# LEDs.net
KiCad netlist of a schematic drawn in Altium Designer
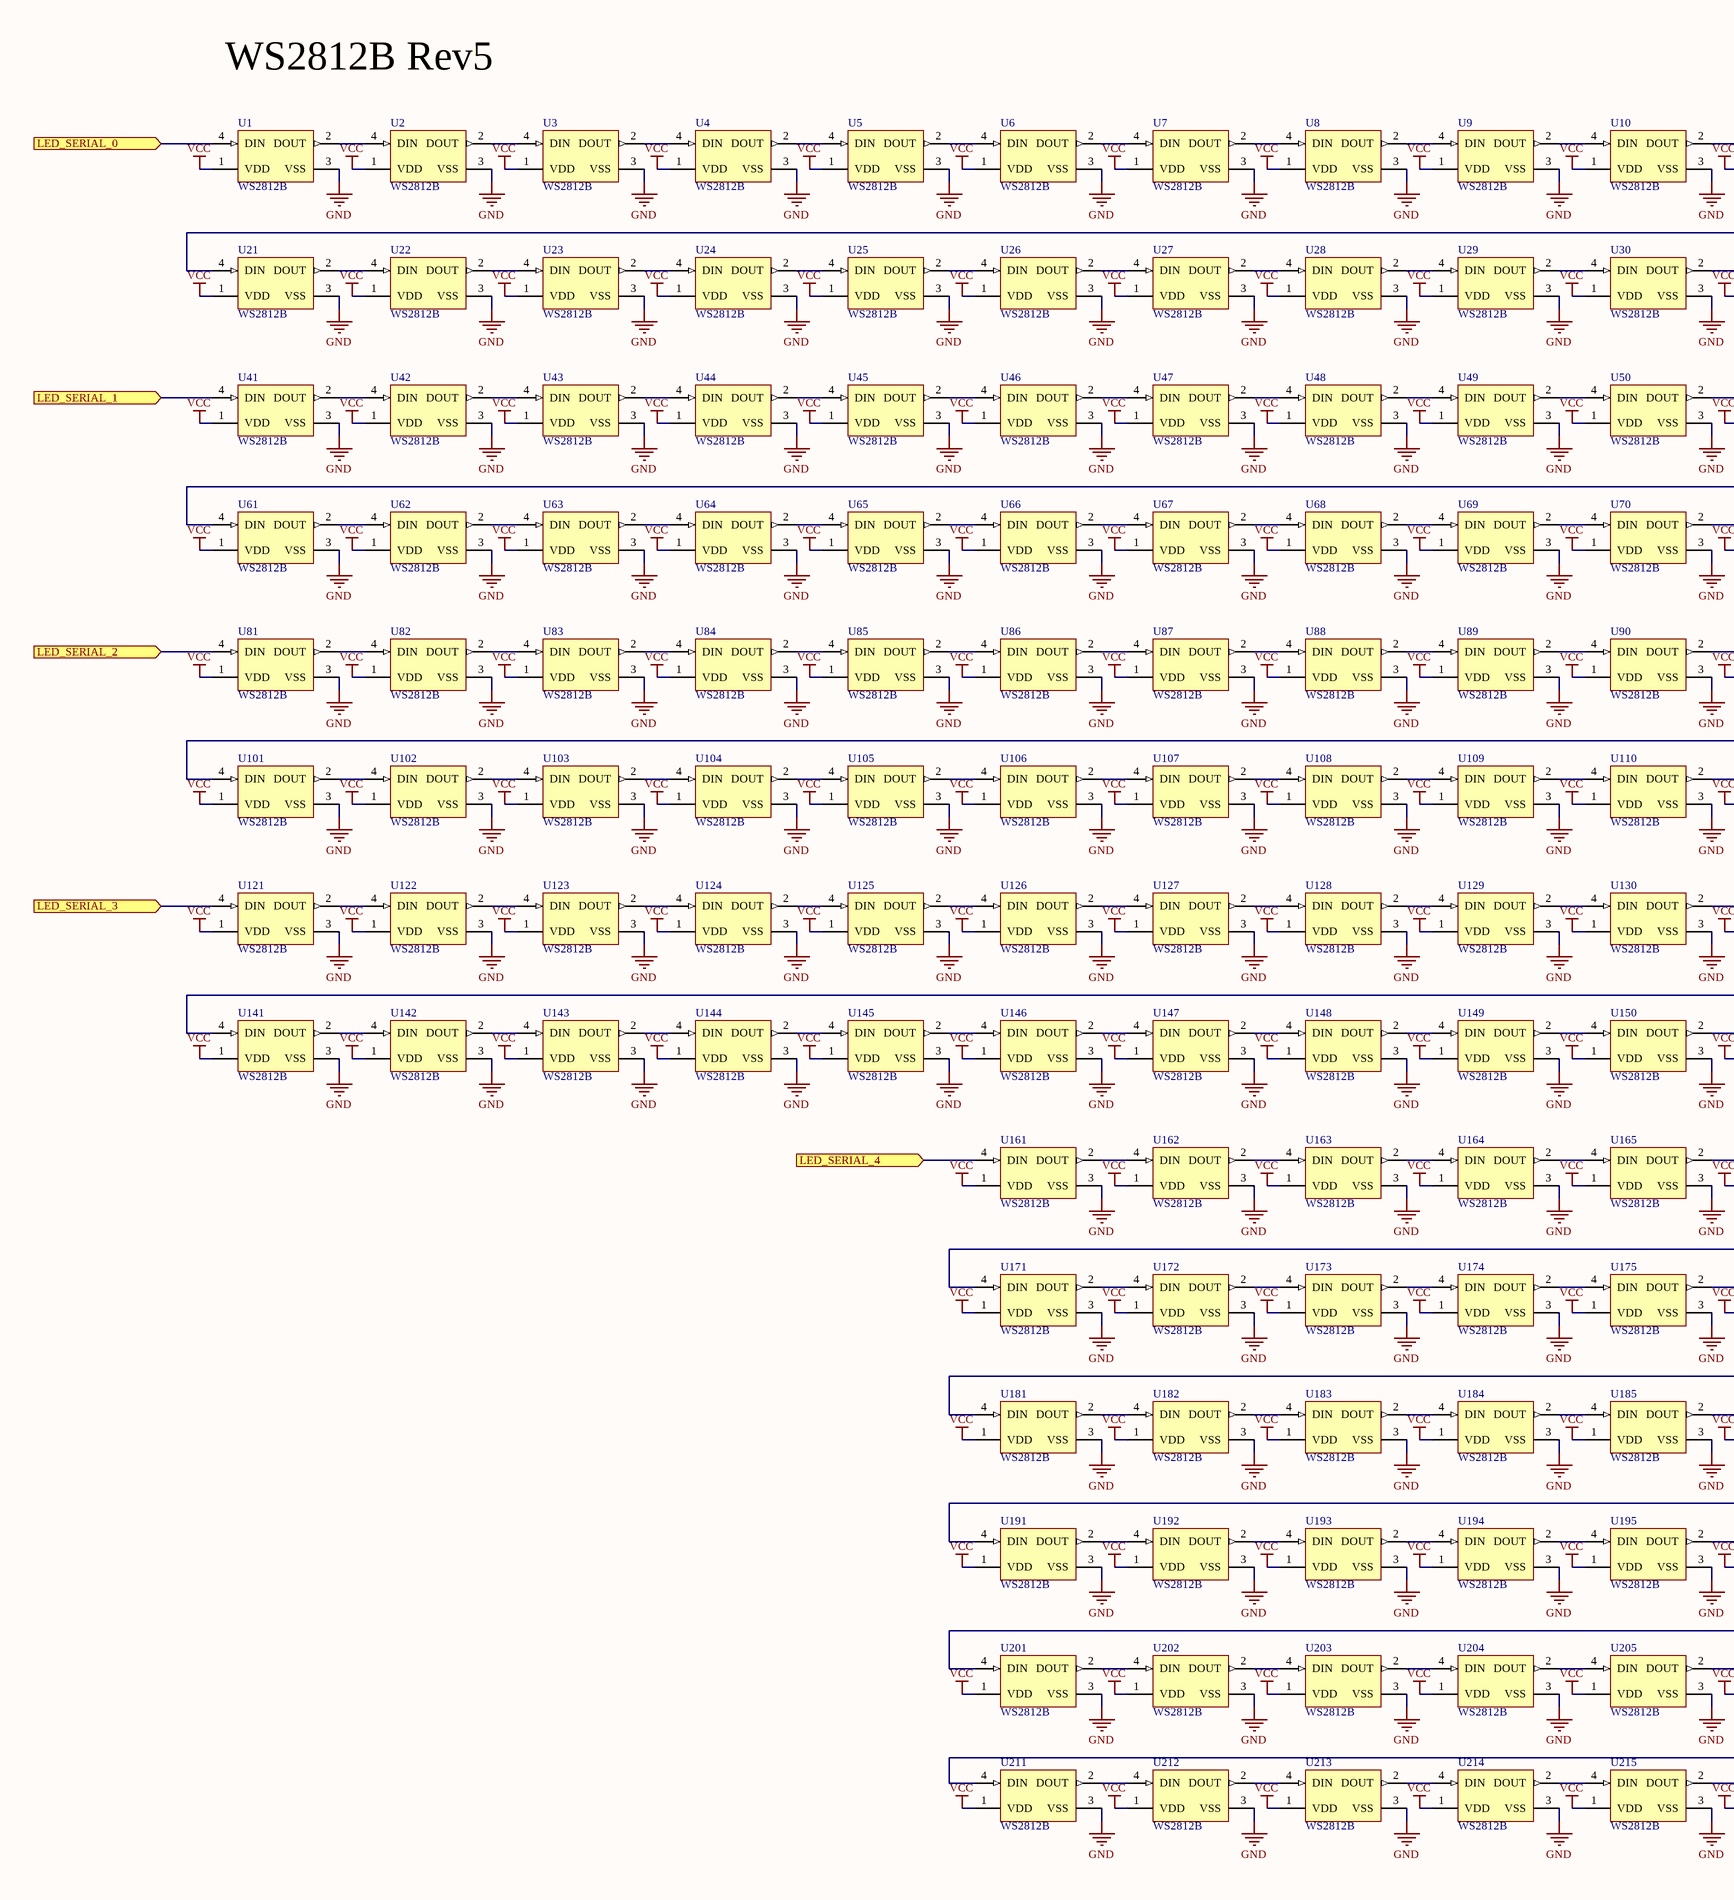
[diagram p0: LEDs.SchDoc, left]
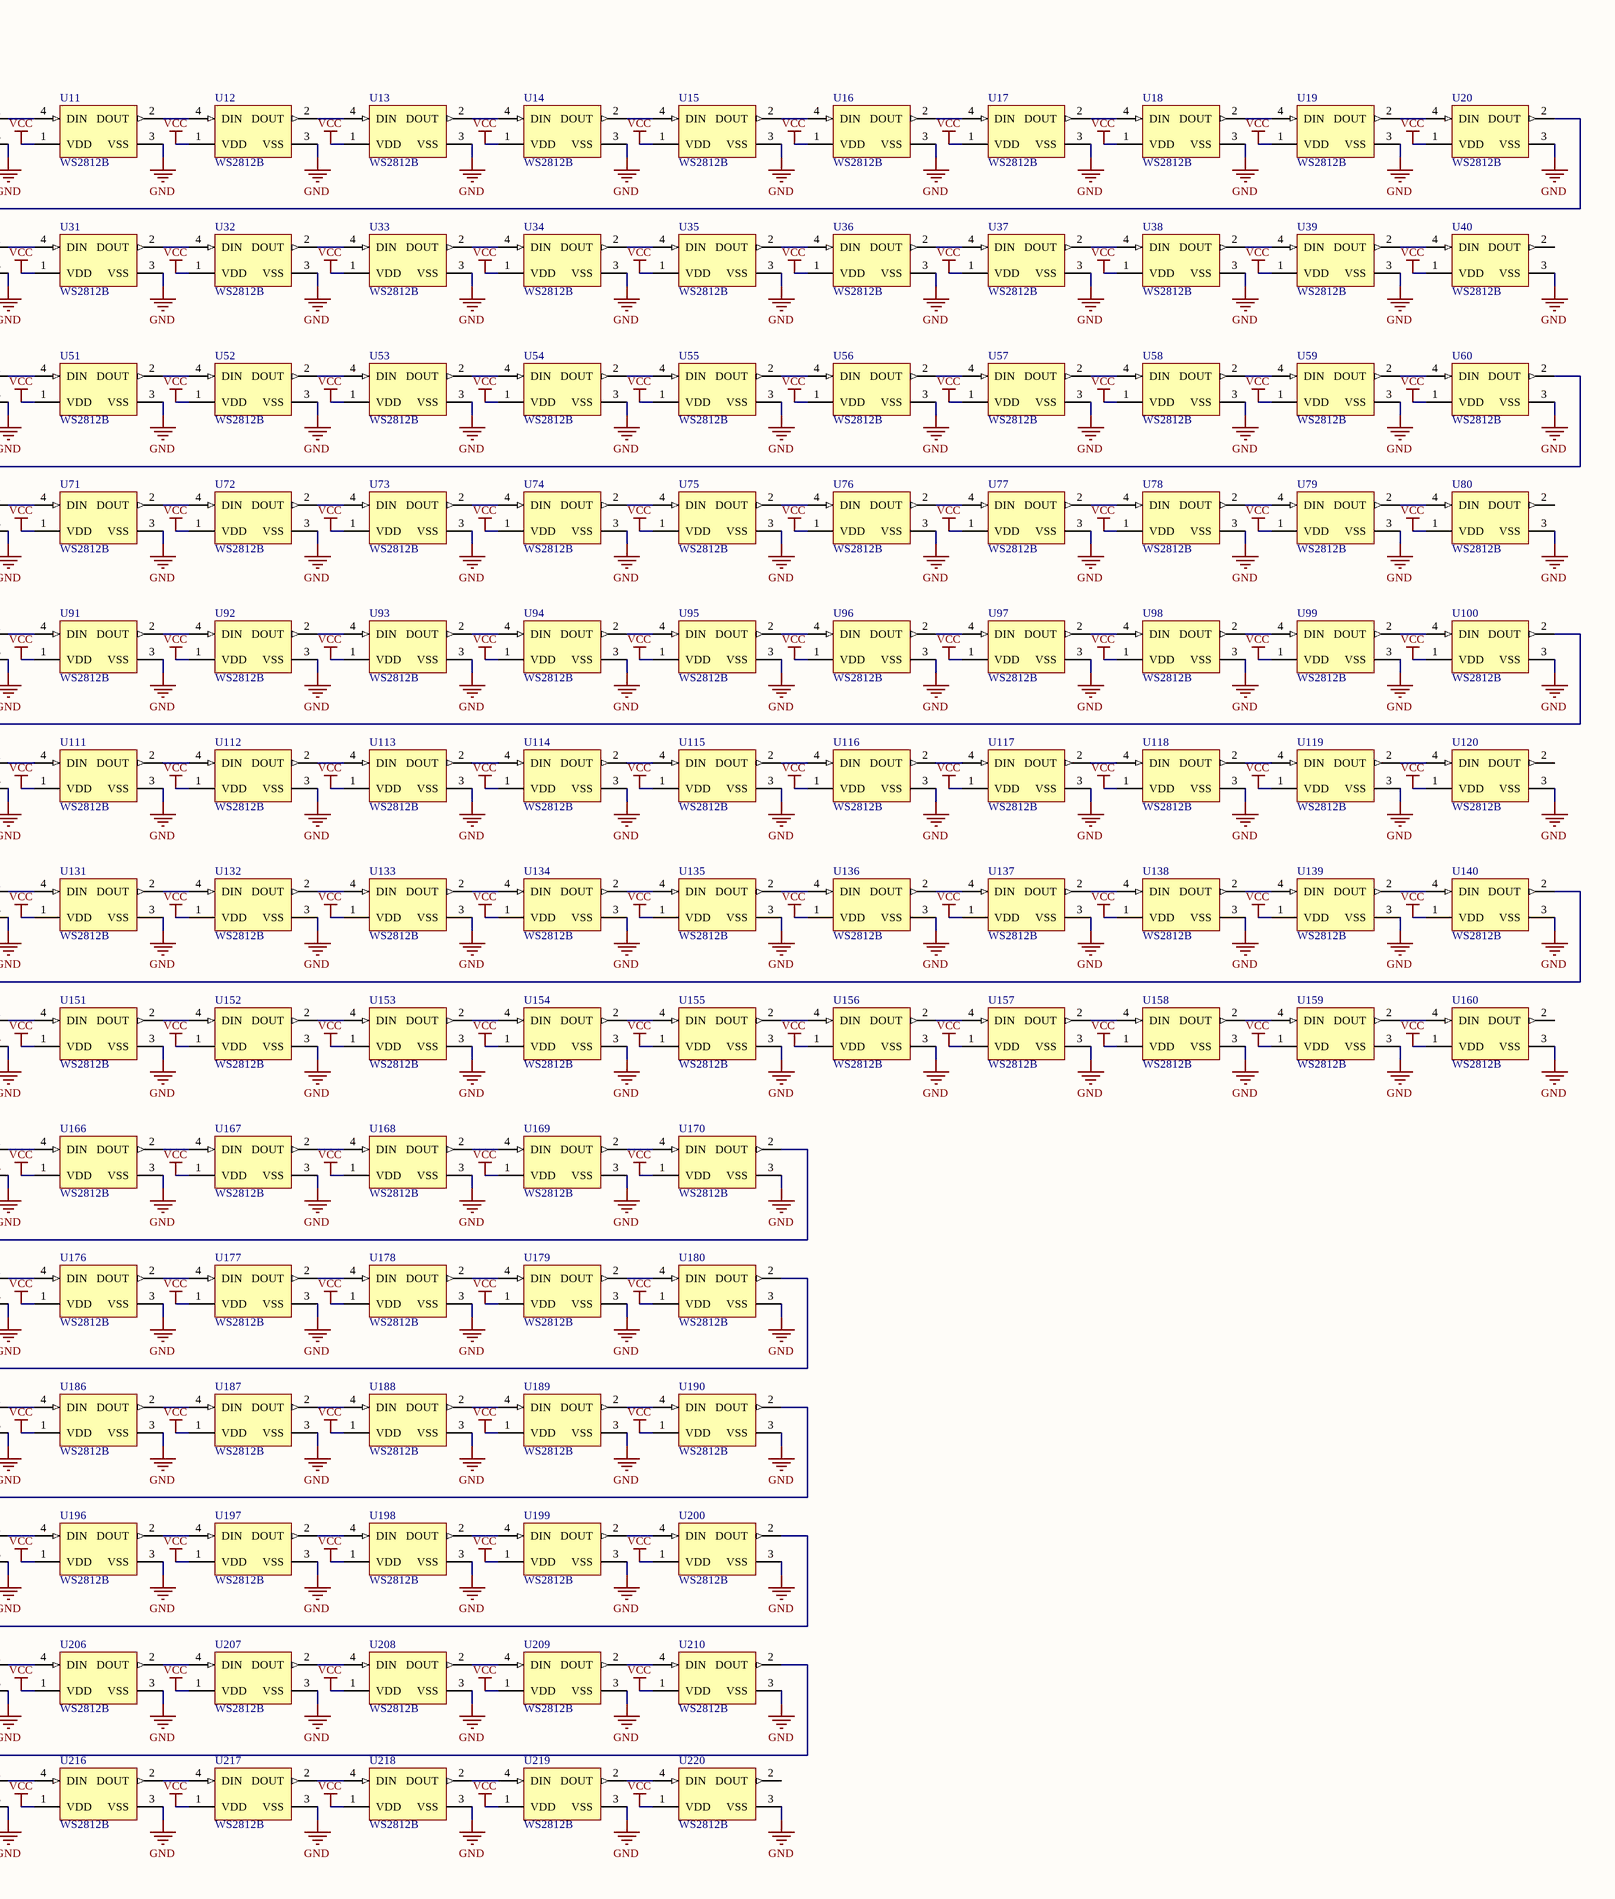
[diagram p1: LEDs.SchDoc, right]

(export (version "E")
  (design (tool "Eeschema 10.0.6"))
  (components
    (comp (ref "U1")
      (value "WS2812B")
      (footprint "LED5050")
      (fields (field (name "MANUFACTURER") "Adafruit-Industries-LLC") (field (name "LCSC PART #") "C114586"))
      (libsource (lib "Schlib1") (part "CMP-2000-05026-1"))
    )
    (comp (ref "U2")
      (value "WS2812B")
      (footprint "LED5050")
      (fields (field (name "MANUFACTURER") "Adafruit-Industries-LLC") (field (name "LCSC PART #") "C114586"))
      (libsource (lib "Schlib1") (part "CMP-2000-05026-1"))
    )
    (comp (ref "U3")
      (value "WS2812B")
      (footprint "LED5050")
      (fields (field (name "MANUFACTURER") "Adafruit-Industries-LLC") (field (name "LCSC PART #") "C114586"))
      (libsource (lib "Schlib1") (part "CMP-2000-05026-1"))
    )
    (comp (ref "U4")
      (value "WS2812B")
      (footprint "LED5050")
      (fields (field (name "MANUFACTURER") "Adafruit-Industries-LLC") (field (name "LCSC PART #") "C114586"))
      (libsource (lib "Schlib1") (part "CMP-2000-05026-1"))
    )
    (comp (ref "U5")
      (value "WS2812B")
      (footprint "LED5050")
      (fields (field (name "MANUFACTURER") "Adafruit-Industries-LLC") (field (name "LCSC PART #") "C114586"))
      (libsource (lib "Schlib1") (part "CMP-2000-05026-1"))
    )
    (comp (ref "U6")
      (value "WS2812B")
      (footprint "LED5050")
      (fields (field (name "MANUFACTURER") "Adafruit-Industries-LLC") (field (name "LCSC PART #") "C114586"))
      (libsource (lib "Schlib1") (part "CMP-2000-05026-1"))
    )
    (comp (ref "U7")
      (value "WS2812B")
      (footprint "LED5050")
      (fields (field (name "MANUFACTURER") "Adafruit-Industries-LLC") (field (name "LCSC PART #") "C114586"))
      (libsource (lib "Schlib1") (part "CMP-2000-05026-1"))
    )
    (comp (ref "U8")
      (value "WS2812B")
      (footprint "LED5050")
      (fields (field (name "MANUFACTURER") "Adafruit-Industries-LLC") (field (name "LCSC PART #") "C114586"))
      (libsource (lib "Schlib1") (part "CMP-2000-05026-1"))
    )
    (comp (ref "U9")
      (value "WS2812B")
      (footprint "LED5050")
      (fields (field (name "MANUFACTURER") "Adafruit-Industries-LLC") (field (name "LCSC PART #") "C114586"))
      (libsource (lib "Schlib1") (part "CMP-2000-05026-1"))
    )
    (comp (ref "U10")
      (value "WS2812B")
      (footprint "LED5050")
      (fields (field (name "MANUFACTURER") "Adafruit-Industries-LLC") (field (name "LCSC PART #") "C114586"))
      (libsource (lib "Schlib1") (part "CMP-2000-05026-1"))
    )
    (comp (ref "U11")
      (value "WS2812B")
      (footprint "LED5050")
      (fields (field (name "MANUFACTURER") "Adafruit-Industries-LLC") (field (name "LCSC PART #") "C114586"))
      (libsource (lib "Schlib1") (part "CMP-2000-05026-1"))
    )
    (comp (ref "U12")
      (value "WS2812B")
      (footprint "LED5050")
      (fields (field (name "MANUFACTURER") "Adafruit-Industries-LLC") (field (name "LCSC PART #") "C114586"))
      (libsource (lib "Schlib1") (part "CMP-2000-05026-1"))
    )
    (comp (ref "U13")
      (value "WS2812B")
      (footprint "LED5050")
      (fields (field (name "MANUFACTURER") "Adafruit-Industries-LLC") (field (name "LCSC PART #") "C114586"))
      (libsource (lib "Schlib1") (part "CMP-2000-05026-1"))
    )
    (comp (ref "U14")
      (value "WS2812B")
      (footprint "LED5050")
      (fields (field (name "MANUFACTURER") "Adafruit-Industries-LLC") (field (name "LCSC PART #") "C114586"))
      (libsource (lib "Schlib1") (part "CMP-2000-05026-1"))
    )
    (comp (ref "U15")
      (value "WS2812B")
      (footprint "LED5050")
      (fields (field (name "MANUFACTURER") "Adafruit-Industries-LLC") (field (name "LCSC PART #") "C114586"))
      (libsource (lib "Schlib1") (part "CMP-2000-05026-1"))
    )
    (comp (ref "U16")
      (value "WS2812B")
      (footprint "LED5050")
      (fields (field (name "MANUFACTURER") "Adafruit-Industries-LLC") (field (name "LCSC PART #") "C114586"))
      (libsource (lib "Schlib1") (part "CMP-2000-05026-1"))
    )
    (comp (ref "U17")
      (value "WS2812B")
      (footprint "LED5050")
      (fields (field (name "MANUFACTURER") "Adafruit-Industries-LLC") (field (name "LCSC PART #") "C114586"))
      (libsource (lib "Schlib1") (part "CMP-2000-05026-1"))
    )
    (comp (ref "U18")
      (value "WS2812B")
      (footprint "LED5050")
      (fields (field (name "MANUFACTURER") "Adafruit-Industries-LLC") (field (name "LCSC PART #") "C114586"))
      (libsource (lib "Schlib1") (part "CMP-2000-05026-1"))
    )
    (comp (ref "U19")
      (value "WS2812B")
      (footprint "LED5050")
      (fields (field (name "MANUFACTURER") "Adafruit-Industries-LLC") (field (name "LCSC PART #") "C114586"))
      (libsource (lib "Schlib1") (part "CMP-2000-05026-1"))
    )
    (comp (ref "U20")
      (value "WS2812B")
      (footprint "LED5050")
      (fields (field (name "MANUFACTURER") "Adafruit-Industries-LLC") (field (name "LCSC PART #") "C114586"))
      (libsource (lib "Schlib1") (part "CMP-2000-05026-1"))
    )
    (comp (ref "U21")
      (value "WS2812B")
      (footprint "LED5050")
      (fields (field (name "MANUFACTURER") "Adafruit-Industries-LLC") (field (name "LCSC PART #") "C114586"))
      (libsource (lib "Schlib1") (part "CMP-2000-05026-1"))
    )
    (comp (ref "U22")
      (value "WS2812B")
      (footprint "LED5050")
      (fields (field (name "MANUFACTURER") "Adafruit-Industries-LLC") (field (name "LCSC PART #") "C114586"))
      (libsource (lib "Schlib1") (part "CMP-2000-05026-1"))
    )
    (comp (ref "U23")
      (value "WS2812B")
      (footprint "LED5050")
      (fields (field (name "MANUFACTURER") "Adafruit-Industries-LLC") (field (name "LCSC PART #") "C114586"))
      (libsource (lib "Schlib1") (part "CMP-2000-05026-1"))
    )
    (comp (ref "U24")
      (value "WS2812B")
      (footprint "LED5050")
      (fields (field (name "MANUFACTURER") "Adafruit-Industries-LLC") (field (name "LCSC PART #") "C114586"))
      (libsource (lib "Schlib1") (part "CMP-2000-05026-1"))
    )
    (comp (ref "U25")
      (value "WS2812B")
      (footprint "LED5050")
      (fields (field (name "MANUFACTURER") "Adafruit-Industries-LLC") (field (name "LCSC PART #") "C114586"))
      (libsource (lib "Schlib1") (part "CMP-2000-05026-1"))
    )
    (comp (ref "U26")
      (value "WS2812B")
      (footprint "LED5050")
      (fields (field (name "MANUFACTURER") "Adafruit-Industries-LLC") (field (name "LCSC PART #") "C114586"))
      (libsource (lib "Schlib1") (part "CMP-2000-05026-1"))
    )
    (comp (ref "U27")
      (value "WS2812B")
      (footprint "LED5050")
      (fields (field (name "MANUFACTURER") "Adafruit-Industries-LLC") (field (name "LCSC PART #") "C114586"))
      (libsource (lib "Schlib1") (part "CMP-2000-05026-1"))
    )
    (comp (ref "U28")
      (value "WS2812B")
      (footprint "LED5050")
      (fields (field (name "MANUFACTURER") "Adafruit-Industries-LLC") (field (name "LCSC PART #") "C114586"))
      (libsource (lib "Schlib1") (part "CMP-2000-05026-1"))
    )
    (comp (ref "U29")
      (value "WS2812B")
      (footprint "LED5050")
      (fields (field (name "MANUFACTURER") "Adafruit-Industries-LLC") (field (name "LCSC PART #") "C114586"))
      (libsource (lib "Schlib1") (part "CMP-2000-05026-1"))
    )
    (comp (ref "U30")
      (value "WS2812B")
      (footprint "LED5050")
      (fields (field (name "MANUFACTURER") "Adafruit-Industries-LLC") (field (name "LCSC PART #") "C114586"))
      (libsource (lib "Schlib1") (part "CMP-2000-05026-1"))
    )
    (comp (ref "U31")
      (value "WS2812B")
      (footprint "LED5050")
      (fields (field (name "MANUFACTURER") "Adafruit-Industries-LLC") (field (name "LCSC PART #") "C114586"))
      (libsource (lib "Schlib1") (part "CMP-2000-05026-1"))
    )
    (comp (ref "U32")
      (value "WS2812B")
      (footprint "LED5050")
      (fields (field (name "MANUFACTURER") "Adafruit-Industries-LLC") (field (name "LCSC PART #") "C114586"))
      (libsource (lib "Schlib1") (part "CMP-2000-05026-1"))
    )
    (comp (ref "U33")
      (value "WS2812B")
      (footprint "LED5050")
      (fields (field (name "MANUFACTURER") "Adafruit-Industries-LLC") (field (name "LCSC PART #") "C114586"))
      (libsource (lib "Schlib1") (part "CMP-2000-05026-1"))
    )
    (comp (ref "U34")
      (value "WS2812B")
      (footprint "LED5050")
      (fields (field (name "MANUFACTURER") "Adafruit-Industries-LLC") (field (name "LCSC PART #") "C114586"))
      (libsource (lib "Schlib1") (part "CMP-2000-05026-1"))
    )
    (comp (ref "U35")
      (value "WS2812B")
      (footprint "LED5050")
      (fields (field (name "MANUFACTURER") "Adafruit-Industries-LLC") (field (name "LCSC PART #") "C114586"))
      (libsource (lib "Schlib1") (part "CMP-2000-05026-1"))
    )
    (comp (ref "U36")
      (value "WS2812B")
      (footprint "LED5050")
      (fields (field (name "MANUFACTURER") "Adafruit-Industries-LLC") (field (name "LCSC PART #") "C114586"))
      (libsource (lib "Schlib1") (part "CMP-2000-05026-1"))
    )
    (comp (ref "U37")
      (value "WS2812B")
      (footprint "LED5050")
      (fields (field (name "MANUFACTURER") "Adafruit-Industries-LLC") (field (name "LCSC PART #") "C114586"))
      (libsource (lib "Schlib1") (part "CMP-2000-05026-1"))
    )
    (comp (ref "U38")
      (value "WS2812B")
      (footprint "LED5050")
      (fields (field (name "MANUFACTURER") "Adafruit-Industries-LLC") (field (name "LCSC PART #") "C114586"))
      (libsource (lib "Schlib1") (part "CMP-2000-05026-1"))
    )
    (comp (ref "U39")
      (value "WS2812B")
      (footprint "LED5050")
      (fields (field (name "MANUFACTURER") "Adafruit-Industries-LLC") (field (name "LCSC PART #") "C114586"))
      (libsource (lib "Schlib1") (part "CMP-2000-05026-1"))
    )
    (comp (ref "U40")
      (value "WS2812B")
      (footprint "LED5050")
      (fields (field (name "MANUFACTURER") "Adafruit-Industries-LLC") (field (name "LCSC PART #") "C114586"))
      (libsource (lib "Schlib1") (part "CMP-2000-05026-1"))
    )
    (comp (ref "U41")
      (value "WS2812B")
      (footprint "LED5050")
      (fields (field (name "MANUFACTURER") "Adafruit-Industries-LLC") (field (name "LCSC PART #") "C114586"))
      (libsource (lib "Schlib1") (part "CMP-2000-05026-1"))
    )
    (comp (ref "U42")
      (value "WS2812B")
      (footprint "LED5050")
      (fields (field (name "MANUFACTURER") "Adafruit-Industries-LLC") (field (name "LCSC PART #") "C114586"))
      (libsource (lib "Schlib1") (part "CMP-2000-05026-1"))
    )
    (comp (ref "U43")
      (value "WS2812B")
      (footprint "LED5050")
      (fields (field (name "MANUFACTURER") "Adafruit-Industries-LLC") (field (name "LCSC PART #") "C114586"))
      (libsource (lib "Schlib1") (part "CMP-2000-05026-1"))
    )
    (comp (ref "U44")
      (value "WS2812B")
      (footprint "LED5050")
      (fields (field (name "MANUFACTURER") "Adafruit-Industries-LLC") (field (name "LCSC PART #") "C114586"))
      (libsource (lib "Schlib1") (part "CMP-2000-05026-1"))
    )
    (comp (ref "U45")
      (value "WS2812B")
      (footprint "LED5050")
      (fields (field (name "MANUFACTURER") "Adafruit-Industries-LLC") (field (name "LCSC PART #") "C114586"))
      (libsource (lib "Schlib1") (part "CMP-2000-05026-1"))
    )
    (comp (ref "U46")
      (value "WS2812B")
      (footprint "LED5050")
      (fields (field (name "MANUFACTURER") "Adafruit-Industries-LLC") (field (name "LCSC PART #") "C114586"))
      (libsource (lib "Schlib1") (part "CMP-2000-05026-1"))
    )
    (comp (ref "U47")
      (value "WS2812B")
      (footprint "LED5050")
      (fields (field (name "MANUFACTURER") "Adafruit-Industries-LLC") (field (name "LCSC PART #") "C114586"))
      (libsource (lib "Schlib1") (part "CMP-2000-05026-1"))
    )
    (comp (ref "U48")
      (value "WS2812B")
      (footprint "LED5050")
      (fields (field (name "MANUFACTURER") "Adafruit-Industries-LLC") (field (name "LCSC PART #") "C114586"))
      (libsource (lib "Schlib1") (part "CMP-2000-05026-1"))
    )
    (comp (ref "U49")
      (value "WS2812B")
      (footprint "LED5050")
      (fields (field (name "MANUFACTURER") "Adafruit-Industries-LLC") (field (name "LCSC PART #") "C114586"))
      (libsource (lib "Schlib1") (part "CMP-2000-05026-1"))
    )
    (comp (ref "U50")
      (value "WS2812B")
      (footprint "LED5050")
      (fields (field (name "MANUFACTURER") "Adafruit-Industries-LLC") (field (name "LCSC PART #") "C114586"))
      (libsource (lib "Schlib1") (part "CMP-2000-05026-1"))
    )
    (comp (ref "U51")
      (value "WS2812B")
      (footprint "LED5050")
      (fields (field (name "MANUFACTURER") "Adafruit-Industries-LLC") (field (name "LCSC PART #") "C114586"))
      (libsource (lib "Schlib1") (part "CMP-2000-05026-1"))
    )
    (comp (ref "U52")
      (value "WS2812B")
      (footprint "LED5050")
      (fields (field (name "MANUFACTURER") "Adafruit-Industries-LLC") (field (name "LCSC PART #") "C114586"))
      (libsource (lib "Schlib1") (part "CMP-2000-05026-1"))
    )
    (comp (ref "U53")
      (value "WS2812B")
      (footprint "LED5050")
      (fields (field (name "MANUFACTURER") "Adafruit-Industries-LLC") (field (name "LCSC PART #") "C114586"))
      (libsource (lib "Schlib1") (part "CMP-2000-05026-1"))
    )
    (comp (ref "U54")
      (value "WS2812B")
      (footprint "LED5050")
      (fields (field (name "MANUFACTURER") "Adafruit-Industries-LLC") (field (name "LCSC PART #") "C114586"))
      (libsource (lib "Schlib1") (part "CMP-2000-05026-1"))
    )
    (comp (ref "U55")
      (value "WS2812B")
      (footprint "LED5050")
      (fields (field (name "MANUFACTURER") "Adafruit-Industries-LLC") (field (name "LCSC PART #") "C114586"))
      (libsource (lib "Schlib1") (part "CMP-2000-05026-1"))
    )
    (comp (ref "U56")
      (value "WS2812B")
      (footprint "LED5050")
      (fields (field (name "MANUFACTURER") "Adafruit-Industries-LLC") (field (name "LCSC PART #") "C114586"))
      (libsource (lib "Schlib1") (part "CMP-2000-05026-1"))
    )
    (comp (ref "U57")
      (value "WS2812B")
      (footprint "LED5050")
      (fields (field (name "MANUFACTURER") "Adafruit-Industries-LLC") (field (name "LCSC PART #") "C114586"))
      (libsource (lib "Schlib1") (part "CMP-2000-05026-1"))
    )
    (comp (ref "U58")
      (value "WS2812B")
      (footprint "LED5050")
      (fields (field (name "MANUFACTURER") "Adafruit-Industries-LLC") (field (name "LCSC PART #") "C114586"))
      (libsource (lib "Schlib1") (part "CMP-2000-05026-1"))
    )
    (comp (ref "U59")
      (value "WS2812B")
      (footprint "LED5050")
      (fields (field (name "MANUFACTURER") "Adafruit-Industries-LLC") (field (name "LCSC PART #") "C114586"))
      (libsource (lib "Schlib1") (part "CMP-2000-05026-1"))
    )
    (comp (ref "U60")
      (value "WS2812B")
      (footprint "LED5050")
      (fields (field (name "MANUFACTURER") "Adafruit-Industries-LLC") (field (name "LCSC PART #") "C114586"))
      (libsource (lib "Schlib1") (part "CMP-2000-05026-1"))
    )
    (comp (ref "U61")
      (value "WS2812B")
      (footprint "LED5050")
      (fields (field (name "MANUFACTURER") "Adafruit-Industries-LLC") (field (name "LCSC PART #") "C114586"))
      (libsource (lib "Schlib1") (part "CMP-2000-05026-1"))
    )
    (comp (ref "U62")
      (value "WS2812B")
      (footprint "LED5050")
      (fields (field (name "MANUFACTURER") "Adafruit-Industries-LLC") (field (name "LCSC PART #") "C114586"))
      (libsource (lib "Schlib1") (part "CMP-2000-05026-1"))
    )
    (comp (ref "U63")
      (value "WS2812B")
      (footprint "LED5050")
      (fields (field (name "MANUFACTURER") "Adafruit-Industries-LLC") (field (name "LCSC PART #") "C114586"))
      (libsource (lib "Schlib1") (part "CMP-2000-05026-1"))
    )
    (comp (ref "U64")
      (value "WS2812B")
      (footprint "LED5050")
      (fields (field (name "MANUFACTURER") "Adafruit-Industries-LLC") (field (name "LCSC PART #") "C114586"))
      (libsource (lib "Schlib1") (part "CMP-2000-05026-1"))
    )
    (comp (ref "U65")
      (value "WS2812B")
      (footprint "LED5050")
      (fields (field (name "MANUFACTURER") "Adafruit-Industries-LLC") (field (name "LCSC PART #") "C114586"))
      (libsource (lib "Schlib1") (part "CMP-2000-05026-1"))
    )
    (comp (ref "U66")
      (value "WS2812B")
      (footprint "LED5050")
      (fields (field (name "MANUFACTURER") "Adafruit-Industries-LLC") (field (name "LCSC PART #") "C114586"))
      (libsource (lib "Schlib1") (part "CMP-2000-05026-1"))
    )
    (comp (ref "U67")
      (value "WS2812B")
      (footprint "LED5050")
      (fields (field (name "MANUFACTURER") "Adafruit-Industries-LLC") (field (name "LCSC PART #") "C114586"))
      (libsource (lib "Schlib1") (part "CMP-2000-05026-1"))
    )
    (comp (ref "U68")
      (value "WS2812B")
      (footprint "LED5050")
      (fields (field (name "MANUFACTURER") "Adafruit-Industries-LLC") (field (name "LCSC PART #") "C114586"))
      (libsource (lib "Schlib1") (part "CMP-2000-05026-1"))
    )
    (comp (ref "U69")
      (value "WS2812B")
      (footprint "LED5050")
      (fields (field (name "MANUFACTURER") "Adafruit-Industries-LLC") (field (name "LCSC PART #") "C114586"))
      (libsource (lib "Schlib1") (part "CMP-2000-05026-1"))
    )
    (comp (ref "U70")
      (value "WS2812B")
      (footprint "LED5050")
      (fields (field (name "MANUFACTURER") "Adafruit-Industries-LLC") (field (name "LCSC PART #") "C114586"))
      (libsource (lib "Schlib1") (part "CMP-2000-05026-1"))
    )
    (comp (ref "U71")
      (value "WS2812B")
      (footprint "LED5050")
      (fields (field (name "MANUFACTURER") "Adafruit-Industries-LLC") (field (name "LCSC PART #") "C114586"))
      (libsource (lib "Schlib1") (part "CMP-2000-05026-1"))
    )
    (comp (ref "U72")
      (value "WS2812B")
      (footprint "LED5050")
      (fields (field (name "MANUFACTURER") "Adafruit-Industries-LLC") (field (name "LCSC PART #") "C114586"))
      (libsource (lib "Schlib1") (part "CMP-2000-05026-1"))
    )
    (comp (ref "U73")
      (value "WS2812B")
      (footprint "LED5050")
      (fields (field (name "MANUFACTURER") "Adafruit-Industries-LLC") (field (name "LCSC PART #") "C114586"))
      (libsource (lib "Schlib1") (part "CMP-2000-05026-1"))
    )
    (comp (ref "U74")
      (value "WS2812B")
      (footprint "LED5050")
      (fields (field (name "MANUFACTURER") "Adafruit-Industries-LLC") (field (name "LCSC PART #") "C114586"))
      (libsource (lib "Schlib1") (part "CMP-2000-05026-1"))
    )
    (comp (ref "U75")
      (value "WS2812B")
      (footprint "LED5050")
      (fields (field (name "MANUFACTURER") "Adafruit-Industries-LLC") (field (name "LCSC PART #") "C114586"))
      (libsource (lib "Schlib1") (part "CMP-2000-05026-1"))
    )
    (comp (ref "U76")
      (value "WS2812B")
      (footprint "LED5050")
      (fields (field (name "MANUFACTURER") "Adafruit-Industries-LLC") (field (name "LCSC PART #") "C114586"))
      (libsource (lib "Schlib1") (part "CMP-2000-05026-1"))
    )
    (comp (ref "U77")
      (value "WS2812B")
      (footprint "LED5050")
      (fields (field (name "MANUFACTURER") "Adafruit-Industries-LLC") (field (name "LCSC PART #") "C114586"))
      (libsource (lib "Schlib1") (part "CMP-2000-05026-1"))
    )
    (comp (ref "U78")
      (value "WS2812B")
      (footprint "LED5050")
      (fields (field (name "MANUFACTURER") "Adafruit-Industries-LLC") (field (name "LCSC PART #") "C114586"))
      (libsource (lib "Schlib1") (part "CMP-2000-05026-1"))
    )
    (comp (ref "U79")
      (value "WS2812B")
      (footprint "LED5050")
      (fields (field (name "MANUFACTURER") "Adafruit-Industries-LLC") (field (name "LCSC PART #") "C114586"))
      (libsource (lib "Schlib1") (part "CMP-2000-05026-1"))
    )
    (comp (ref "U80")
      (value "WS2812B")
      (footprint "LED5050")
      (fields (field (name "MANUFACTURER") "Adafruit-Industries-LLC") (field (name "LCSC PART #") "C114586"))
      (libsource (lib "Schlib1") (part "CMP-2000-05026-1"))
    )
    (comp (ref "U81")
      (value "WS2812B")
      (footprint "LED5050")
      (fields (field (name "MANUFACTURER") "Adafruit-Industries-LLC") (field (name "LCSC PART #") "C114586"))
      (libsource (lib "Schlib1") (part "CMP-2000-05026-1"))
    )
    (comp (ref "U82")
      (value "WS2812B")
      (footprint "LED5050")
      (fields (field (name "MANUFACTURER") "Adafruit-Industries-LLC") (field (name "LCSC PART #") "C114586"))
      (libsource (lib "Schlib1") (part "CMP-2000-05026-1"))
    )
    (comp (ref "U83")
      (value "WS2812B")
      (footprint "LED5050")
      (fields (field (name "MANUFACTURER") "Adafruit-Industries-LLC") (field (name "LCSC PART #") "C114586"))
      (libsource (lib "Schlib1") (part "CMP-2000-05026-1"))
    )
    (comp (ref "U84")
      (value "WS2812B")
      (footprint "LED5050")
      (fields (field (name "MANUFACTURER") "Adafruit-Industries-LLC") (field (name "LCSC PART #") "C114586"))
      (libsource (lib "Schlib1") (part "CMP-2000-05026-1"))
    )
    (comp (ref "U85")
      (value "WS2812B")
      (footprint "LED5050")
      (fields (field (name "MANUFACTURER") "Adafruit-Industries-LLC") (field (name "LCSC PART #") "C114586"))
      (libsource (lib "Schlib1") (part "CMP-2000-05026-1"))
    )
    (comp (ref "U86")
      (value "WS2812B")
      (footprint "LED5050")
      (fields (field (name "MANUFACTURER") "Adafruit-Industries-LLC") (field (name "LCSC PART #") "C114586"))
      (libsource (lib "Schlib1") (part "CMP-2000-05026-1"))
    )
    (comp (ref "U87")
      (value "WS2812B")
      (footprint "LED5050")
      (fields (field (name "MANUFACTURER") "Adafruit-Industries-LLC") (field (name "LCSC PART #") "C114586"))
      (libsource (lib "Schlib1") (part "CMP-2000-05026-1"))
    )
    (comp (ref "U88")
      (value "WS2812B")
      (footprint "LED5050")
      (fields (field (name "MANUFACTURER") "Adafruit-Industries-LLC") (field (name "LCSC PART #") "C114586"))
      (libsource (lib "Schlib1") (part "CMP-2000-05026-1"))
    )
    (comp (ref "U89")
      (value "WS2812B")
      (footprint "LED5050")
      (fields (field (name "MANUFACTURER") "Adafruit-Industries-LLC") (field (name "LCSC PART #") "C114586"))
      (libsource (lib "Schlib1") (part "CMP-2000-05026-1"))
    )
    (comp (ref "U90")
      (value "WS2812B")
      (footprint "LED5050")
      (fields (field (name "MANUFACTURER") "Adafruit-Industries-LLC") (field (name "LCSC PART #") "C114586"))
      (libsource (lib "Schlib1") (part "CMP-2000-05026-1"))
    )
    (comp (ref "U91")
      (value "WS2812B")
      (footprint "LED5050")
      (fields (field (name "MANUFACTURER") "Adafruit-Industries-LLC") (field (name "LCSC PART #") "C114586"))
      (libsource (lib "Schlib1") (part "CMP-2000-05026-1"))
    )
    (comp (ref "U92")
      (value "WS2812B")
      (footprint "LED5050")
      (fields (field (name "MANUFACTURER") "Adafruit-Industries-LLC") (field (name "LCSC PART #") "C114586"))
      (libsource (lib "Schlib1") (part "CMP-2000-05026-1"))
    )
    (comp (ref "U93")
      (value "WS2812B")
      (footprint "LED5050")
      (fields (field (name "MANUFACTURER") "Adafruit-Industries-LLC") (field (name "LCSC PART #") "C114586"))
      (libsource (lib "Schlib1") (part "CMP-2000-05026-1"))
    )
    (comp (ref "U94")
      (value "WS2812B")
      (footprint "LED5050")
      (fields (field (name "MANUFACTURER") "Adafruit-Industries-LLC") (field (name "LCSC PART #") "C114586"))
      (libsource (lib "Schlib1") (part "CMP-2000-05026-1"))
    )
    (comp (ref "U95")
      (value "WS2812B")
      (footprint "LED5050")
      (fields (field (name "MANUFACTURER") "Adafruit-Industries-LLC") (field (name "LCSC PART #") "C114586"))
      (libsource (lib "Schlib1") (part "CMP-2000-05026-1"))
    )
    (comp (ref "U96")
      (value "WS2812B")
      (footprint "LED5050")
      (fields (field (name "MANUFACTURER") "Adafruit-Industries-LLC") (field (name "LCSC PART #") "C114586"))
      (libsource (lib "Schlib1") (part "CMP-2000-05026-1"))
    )
    (comp (ref "U97")
      (value "WS2812B")
      (footprint "LED5050")
      (fields (field (name "MANUFACTURER") "Adafruit-Industries-LLC") (field (name "LCSC PART #") "C114586"))
      (libsource (lib "Schlib1") (part "CMP-2000-05026-1"))
    )
    (comp (ref "U98")
      (value "WS2812B")
      (footprint "LED5050")
      (fields (field (name "MANUFACTURER") "Adafruit-Industries-LLC") (field (name "LCSC PART #") "C114586"))
      (libsource (lib "Schlib1") (part "CMP-2000-05026-1"))
    )
    (comp (ref "U99")
      (value "WS2812B")
      (footprint "LED5050")
      (fields (field (name "MANUFACTURER") "Adafruit-Industries-LLC") (field (name "LCSC PART #") "C114586"))
      (libsource (lib "Schlib1") (part "CMP-2000-05026-1"))
    )
    (comp (ref "U100")
      (value "WS2812B")
      (footprint "LED5050")
      (fields (field (name "MANUFACTURER") "Adafruit-Industries-LLC") (field (name "LCSC PART #") "C114586"))
      (libsource (lib "Schlib1") (part "CMP-2000-05026-1"))
    )
    (comp (ref "U101")
      (value "WS2812B")
      (footprint "LED5050")
      (fields (field (name "MANUFACTURER") "Adafruit-Industries-LLC") (field (name "LCSC PART #") "C114586"))
      (libsource (lib "Schlib1") (part "CMP-2000-05026-1"))
    )
    (comp (ref "U102")
      (value "WS2812B")
      (footprint "LED5050")
      (fields (field (name "MANUFACTURER") "Adafruit-Industries-LLC") (field (name "LCSC PART #") "C114586"))
      (libsource (lib "Schlib1") (part "CMP-2000-05026-1"))
    )
    (comp (ref "U103")
      (value "WS2812B")
      (footprint "LED5050")
      (fields (field (name "MANUFACTURER") "Adafruit-Industries-LLC") (field (name "LCSC PART #") "C114586"))
      (libsource (lib "Schlib1") (part "CMP-2000-05026-1"))
    )
    (comp (ref "U104")
      (value "WS2812B")
      (footprint "LED5050")
      (fields (field (name "MANUFACTURER") "Adafruit-Industries-LLC") (field (name "LCSC PART #") "C114586"))
      (libsource (lib "Schlib1") (part "CMP-2000-05026-1"))
    )
    (comp (ref "U105")
      (value "WS2812B")
      (footprint "LED5050")
      (fields (field (name "MANUFACTURER") "Adafruit-Industries-LLC") (field (name "LCSC PART #") "C114586"))
      (libsource (lib "Schlib1") (part "CMP-2000-05026-1"))
    )
    (comp (ref "U106")
      (value "WS2812B")
      (footprint "LED5050")
      (fields (field (name "MANUFACTURER") "Adafruit-Industries-LLC") (field (name "LCSC PART #") "C114586"))
      (libsource (lib "Schlib1") (part "CMP-2000-05026-1"))
    )
    (comp (ref "U107")
      (value "WS2812B")
      (footprint "LED5050")
      (fields (field (name "MANUFACTURER") "Adafruit-Industries-LLC") (field (name "LCSC PART #") "C114586"))
      (libsource (lib "Schlib1") (part "CMP-2000-05026-1"))
    )
    (comp (ref "U108")
      (value "WS2812B")
      (footprint "LED5050")
      (fields (field (name "MANUFACTURER") "Adafruit-Industries-LLC") (field (name "LCSC PART #") "C114586"))
      (libsource (lib "Schlib1") (part "CMP-2000-05026-1"))
    )
    (comp (ref "U109")
      (value "WS2812B")
      (footprint "LED5050")
      (fields (field (name "MANUFACTURER") "Adafruit-Industries-LLC") (field (name "LCSC PART #") "C114586"))
      (libsource (lib "Schlib1") (part "CMP-2000-05026-1"))
    )
    (comp (ref "U110")
      (value "WS2812B")
      (footprint "LED5050")
      (fields (field (name "MANUFACTURER") "Adafruit-Industries-LLC") (field (name "LCSC PART #") "C114586"))
      (libsource (lib "Schlib1") (part "CMP-2000-05026-1"))
    )
    (comp (ref "U111")
      (value "WS2812B")
      (footprint "LED5050")
      (fields (field (name "MANUFACTURER") "Adafruit-Industries-LLC") (field (name "LCSC PART #") "C114586"))
      (libsource (lib "Schlib1") (part "CMP-2000-05026-1"))
    )
    (comp (ref "U112")
      (value "WS2812B")
      (footprint "LED5050")
      (fields (field (name "MANUFACTURER") "Adafruit-Industries-LLC") (field (name "LCSC PART #") "C114586"))
      (libsource (lib "Schlib1") (part "CMP-2000-05026-1"))
    )
    (comp (ref "U113")
      (value "WS2812B")
      (footprint "LED5050")
      (fields (field (name "MANUFACTURER") "Adafruit-Industries-LLC") (field (name "LCSC PART #") "C114586"))
      (libsource (lib "Schlib1") (part "CMP-2000-05026-1"))
    )
    (comp (ref "U114")
      (value "WS2812B")
      (footprint "LED5050")
      (fields (field (name "MANUFACTURER") "Adafruit-Industries-LLC") (field (name "LCSC PART #") "C114586"))
      (libsource (lib "Schlib1") (part "CMP-2000-05026-1"))
    )
    (comp (ref "U115")
      (value "WS2812B")
      (footprint "LED5050")
      (fields (field (name "MANUFACTURER") "Adafruit-Industries-LLC") (field (name "LCSC PART #") "C114586"))
      (libsource (lib "Schlib1") (part "CMP-2000-05026-1"))
    )
    (comp (ref "U116")
      (value "WS2812B")
      (footprint "LED5050")
      (fields (field (name "MANUFACTURER") "Adafruit-Industries-LLC") (field (name "LCSC PART #") "C114586"))
      (libsource (lib "Schlib1") (part "CMP-2000-05026-1"))
    )
    (comp (ref "U117")
      (value "WS2812B")
      (footprint "LED5050")
      (fields (field (name "MANUFACTURER") "Adafruit-Industries-LLC") (field (name "LCSC PART #") "C114586"))
      (libsource (lib "Schlib1") (part "CMP-2000-05026-1"))
    )
    (comp (ref "U118")
      (value "WS2812B")
      (footprint "LED5050")
      (fields (field (name "MANUFACTURER") "Adafruit-Industries-LLC") (field (name "LCSC PART #") "C114586"))
      (libsource (lib "Schlib1") (part "CMP-2000-05026-1"))
    )
    (comp (ref "U119")
      (value "WS2812B")
      (footprint "LED5050")
      (fields (field (name "MANUFACTURER") "Adafruit-Industries-LLC") (field (name "LCSC PART #") "C114586"))
      (libsource (lib "Schlib1") (part "CMP-2000-05026-1"))
    )
    (comp (ref "U120")
      (value "WS2812B")
      (footprint "LED5050")
      (fields (field (name "MANUFACTURER") "Adafruit-Industries-LLC") (field (name "LCSC PART #") "C114586"))
      (libsource (lib "Schlib1") (part "CMP-2000-05026-1"))
    )
    (comp (ref "U121")
      (value "WS2812B")
      (footprint "LED5050")
      (fields (field (name "MANUFACTURER") "Adafruit-Industries-LLC") (field (name "LCSC PART #") "C114586"))
      (libsource (lib "Schlib1") (part "CMP-2000-05026-1"))
    )
    (comp (ref "U122")
      (value "WS2812B")
      (footprint "LED5050")
      (fields (field (name "MANUFACTURER") "Adafruit-Industries-LLC") (field (name "LCSC PART #") "C114586"))
      (libsource (lib "Schlib1") (part "CMP-2000-05026-1"))
    )
    (comp (ref "U123")
      (value "WS2812B")
      (footprint "LED5050")
      (fields (field (name "MANUFACTURER") "Adafruit-Industries-LLC") (field (name "LCSC PART #") "C114586"))
      (libsource (lib "Schlib1") (part "CMP-2000-05026-1"))
    )
    (comp (ref "U124")
      (value "WS2812B")
      (footprint "LED5050")
      (fields (field (name "MANUFACTURER") "Adafruit-Industries-LLC") (field (name "LCSC PART #") "C114586"))
      (libsource (lib "Schlib1") (part "CMP-2000-05026-1"))
    )
    (comp (ref "U125")
      (value "WS2812B")
      (footprint "LED5050")
      (fields (field (name "MANUFACTURER") "Adafruit-Industries-LLC") (field (name "LCSC PART #") "C114586"))
      (libsource (lib "Schlib1") (part "CMP-2000-05026-1"))
    )
    (comp (ref "U126")
      (value "WS2812B")
      (footprint "LED5050")
      (fields (field (name "MANUFACTURER") "Adafruit-Industries-LLC") (field (name "LCSC PART #") "C114586"))
      (libsource (lib "Schlib1") (part "CMP-2000-05026-1"))
    )
    (comp (ref "U127")
      (value "WS2812B")
      (footprint "LED5050")
      (fields (field (name "MANUFACTURER") "Adafruit-Industries-LLC") (field (name "LCSC PART #") "C114586"))
      (libsource (lib "Schlib1") (part "CMP-2000-05026-1"))
    )
    (comp (ref "U128")
      (value "WS2812B")
      (footprint "LED5050")
      (fields (field (name "MANUFACTURER") "Adafruit-Industries-LLC") (field (name "LCSC PART #") "C114586"))
      (libsource (lib "Schlib1") (part "CMP-2000-05026-1"))
    )
    (comp (ref "U129")
      (value "WS2812B")
      (footprint "LED5050")
      (fields (field (name "MANUFACTURER") "Adafruit-Industries-LLC") (field (name "LCSC PART #") "C114586"))
      (libsource (lib "Schlib1") (part "CMP-2000-05026-1"))
    )
    (comp (ref "U130")
      (value "WS2812B")
      (footprint "LED5050")
      (fields (field (name "MANUFACTURER") "Adafruit-Industries-LLC") (field (name "LCSC PART #") "C114586"))
      (libsource (lib "Schlib1") (part "CMP-2000-05026-1"))
    )
    (comp (ref "U131")
      (value "WS2812B")
      (footprint "LED5050")
      (fields (field (name "MANUFACTURER") "Adafruit-Industries-LLC") (field (name "LCSC PART #") "C114586"))
      (libsource (lib "Schlib1") (part "CMP-2000-05026-1"))
    )
    (comp (ref "U132")
      (value "WS2812B")
      (footprint "LED5050")
      (fields (field (name "MANUFACTURER") "Adafruit-Industries-LLC") (field (name "LCSC PART #") "C114586"))
      (libsource (lib "Schlib1") (part "CMP-2000-05026-1"))
    )
    (comp (ref "U133")
      (value "WS2812B")
      (footprint "LED5050")
      (fields (field (name "MANUFACTURER") "Adafruit-Industries-LLC") (field (name "LCSC PART #") "C114586"))
      (libsource (lib "Schlib1") (part "CMP-2000-05026-1"))
    )
    (comp (ref "U134")
      (value "WS2812B")
      (footprint "LED5050")
      (fields (field (name "MANUFACTURER") "Adafruit-Industries-LLC") (field (name "LCSC PART #") "C114586"))
      (libsource (lib "Schlib1") (part "CMP-2000-05026-1"))
    )
    (comp (ref "U135")
      (value "WS2812B")
      (footprint "LED5050")
      (fields (field (name "MANUFACTURER") "Adafruit-Industries-LLC") (field (name "LCSC PART #") "C114586"))
      (libsource (lib "Schlib1") (part "CMP-2000-05026-1"))
    )
    (comp (ref "U136")
      (value "WS2812B")
      (footprint "LED5050")
      (fields (field (name "MANUFACTURER") "Adafruit-Industries-LLC") (field (name "LCSC PART #") "C114586"))
      (libsource (lib "Schlib1") (part "CMP-2000-05026-1"))
    )
    (comp (ref "U137")
      (value "WS2812B")
      (footprint "LED5050")
      (fields (field (name "MANUFACTURER") "Adafruit-Industries-LLC") (field (name "LCSC PART #") "C114586"))
      (libsource (lib "Schlib1") (part "CMP-2000-05026-1"))
    )
    (comp (ref "U138")
      (value "WS2812B")
      (footprint "LED5050")
      (fields (field (name "MANUFACTURER") "Adafruit-Industries-LLC") (field (name "LCSC PART #") "C114586"))
      (libsource (lib "Schlib1") (part "CMP-2000-05026-1"))
    )
    (comp (ref "U139")
      (value "WS2812B")
      (footprint "LED5050")
      (fields (field (name "MANUFACTURER") "Adafruit-Industries-LLC") (field (name "LCSC PART #") "C114586"))
      (libsource (lib "Schlib1") (part "CMP-2000-05026-1"))
    )
    (comp (ref "U140")
      (value "WS2812B")
      (footprint "LED5050")
      (fields (field (name "MANUFACTURER") "Adafruit-Industries-LLC") (field (name "LCSC PART #") "C114586"))
      (libsource (lib "Schlib1") (part "CMP-2000-05026-1"))
    )
    (comp (ref "U141")
      (value "WS2812B")
      (footprint "LED5050")
      (fields (field (name "MANUFACTURER") "Adafruit-Industries-LLC") (field (name "LCSC PART #") "C114586"))
      (libsource (lib "Schlib1") (part "CMP-2000-05026-1"))
    )
    (comp (ref "U142")
      (value "WS2812B")
      (footprint "LED5050")
      (fields (field (name "MANUFACTURER") "Adafruit-Industries-LLC") (field (name "LCSC PART #") "C114586"))
      (libsource (lib "Schlib1") (part "CMP-2000-05026-1"))
    )
    (comp (ref "U143")
      (value "WS2812B")
      (footprint "LED5050")
      (fields (field (name "MANUFACTURER") "Adafruit-Industries-LLC") (field (name "LCSC PART #") "C114586"))
      (libsource (lib "Schlib1") (part "CMP-2000-05026-1"))
    )
    (comp (ref "U144")
      (value "WS2812B")
      (footprint "LED5050")
      (fields (field (name "MANUFACTURER") "Adafruit-Industries-LLC") (field (name "LCSC PART #") "C114586"))
      (libsource (lib "Schlib1") (part "CMP-2000-05026-1"))
    )
    (comp (ref "U145")
      (value "WS2812B")
      (footprint "LED5050")
      (fields (field (name "MANUFACTURER") "Adafruit-Industries-LLC") (field (name "LCSC PART #") "C114586"))
      (libsource (lib "Schlib1") (part "CMP-2000-05026-1"))
    )
    (comp (ref "U146")
      (value "WS2812B")
      (footprint "LED5050")
      (fields (field (name "MANUFACTURER") "Adafruit-Industries-LLC") (field (name "LCSC PART #") "C114586"))
      (libsource (lib "Schlib1") (part "CMP-2000-05026-1"))
    )
    (comp (ref "U147")
      (value "WS2812B")
      (footprint "LED5050")
      (fields (field (name "MANUFACTURER") "Adafruit-Industries-LLC") (field (name "LCSC PART #") "C114586"))
      (libsource (lib "Schlib1") (part "CMP-2000-05026-1"))
    )
    (comp (ref "U148")
      (value "WS2812B")
      (footprint "LED5050")
      (fields (field (name "MANUFACTURER") "Adafruit-Industries-LLC") (field (name "LCSC PART #") "C114586"))
      (libsource (lib "Schlib1") (part "CMP-2000-05026-1"))
    )
    (comp (ref "U149")
      (value "WS2812B")
      (footprint "LED5050")
      (fields (field (name "MANUFACTURER") "Adafruit-Industries-LLC") (field (name "LCSC PART #") "C114586"))
      (libsource (lib "Schlib1") (part "CMP-2000-05026-1"))
    )
    (comp (ref "U150")
      (value "WS2812B")
      (footprint "LED5050")
      (fields (field (name "MANUFACTURER") "Adafruit-Industries-LLC") (field (name "LCSC PART #") "C114586"))
      (libsource (lib "Schlib1") (part "CMP-2000-05026-1"))
    )
    (comp (ref "U151")
      (value "WS2812B")
      (footprint "LED5050")
      (fields (field (name "MANUFACTURER") "Adafruit-Industries-LLC") (field (name "LCSC PART #") "C114586"))
      (libsource (lib "Schlib1") (part "CMP-2000-05026-1"))
    )
    (comp (ref "U152")
      (value "WS2812B")
      (footprint "LED5050")
      (fields (field (name "MANUFACTURER") "Adafruit-Industries-LLC") (field (name "LCSC PART #") "C114586"))
      (libsource (lib "Schlib1") (part "CMP-2000-05026-1"))
    )
    (comp (ref "U153")
      (value "WS2812B")
      (footprint "LED5050")
      (fields (field (name "MANUFACTURER") "Adafruit-Industries-LLC") (field (name "LCSC PART #") "C114586"))
      (libsource (lib "Schlib1") (part "CMP-2000-05026-1"))
    )
    (comp (ref "U154")
      (value "WS2812B")
      (footprint "LED5050")
      (fields (field (name "MANUFACTURER") "Adafruit-Industries-LLC") (field (name "LCSC PART #") "C114586"))
      (libsource (lib "Schlib1") (part "CMP-2000-05026-1"))
    )
    (comp (ref "U155")
      (value "WS2812B")
      (footprint "LED5050")
      (fields (field (name "MANUFACTURER") "Adafruit-Industries-LLC") (field (name "LCSC PART #") "C114586"))
      (libsource (lib "Schlib1") (part "CMP-2000-05026-1"))
    )
    (comp (ref "U156")
      (value "WS2812B")
      (footprint "LED5050")
      (fields (field (name "MANUFACTURER") "Adafruit-Industries-LLC") (field (name "LCSC PART #") "C114586"))
      (libsource (lib "Schlib1") (part "CMP-2000-05026-1"))
    )
    (comp (ref "U157")
      (value "WS2812B")
      (footprint "LED5050")
      (fields (field (name "MANUFACTURER") "Adafruit-Industries-LLC") (field (name "LCSC PART #") "C114586"))
      (libsource (lib "Schlib1") (part "CMP-2000-05026-1"))
    )
    (comp (ref "U158")
      (value "WS2812B")
      (footprint "LED5050")
      (fields (field (name "MANUFACTURER") "Adafruit-Industries-LLC") (field (name "LCSC PART #") "C114586"))
      (libsource (lib "Schlib1") (part "CMP-2000-05026-1"))
    )
    (comp (ref "U159")
      (value "WS2812B")
      (footprint "LED5050")
      (fields (field (name "MANUFACTURER") "Adafruit-Industries-LLC") (field (name "LCSC PART #") "C114586"))
      (libsource (lib "Schlib1") (part "CMP-2000-05026-1"))
    )
    (comp (ref "U160")
      (value "WS2812B")
      (footprint "LED5050")
      (fields (field (name "MANUFACTURER") "Adafruit-Industries-LLC") (field (name "LCSC PART #") "C114586"))
      (libsource (lib "Schlib1") (part "CMP-2000-05026-1"))
    )
    (comp (ref "U161")
      (value "WS2812B")
      (footprint "LED5050")
      (fields (field (name "MANUFACTURER") "Adafruit-Industries-LLC") (field (name "LCSC PART #") "C114586"))
      (libsource (lib "Schlib1") (part "CMP-2000-05026-1"))
    )
    (comp (ref "U162")
      (value "WS2812B")
      (footprint "LED5050")
      (fields (field (name "MANUFACTURER") "Adafruit-Industries-LLC") (field (name "LCSC PART #") "C114586"))
      (libsource (lib "Schlib1") (part "CMP-2000-05026-1"))
    )
    (comp (ref "U163")
      (value "WS2812B")
      (footprint "LED5050")
      (fields (field (name "MANUFACTURER") "Adafruit-Industries-LLC") (field (name "LCSC PART #") "C114586"))
      (libsource (lib "Schlib1") (part "CMP-2000-05026-1"))
    )
    (comp (ref "U164")
      (value "WS2812B")
      (footprint "LED5050")
      (fields (field (name "MANUFACTURER") "Adafruit-Industries-LLC") (field (name "LCSC PART #") "C114586"))
      (libsource (lib "Schlib1") (part "CMP-2000-05026-1"))
    )
    (comp (ref "U165")
      (value "WS2812B")
      (footprint "LED5050")
      (fields (field (name "MANUFACTURER") "Adafruit-Industries-LLC") (field (name "LCSC PART #") "C114586"))
      (libsource (lib "Schlib1") (part "CMP-2000-05026-1"))
    )
    (comp (ref "U166")
      (value "WS2812B")
      (footprint "LED5050")
      (fields (field (name "MANUFACTURER") "Adafruit-Industries-LLC") (field (name "LCSC PART #") "C114586"))
      (libsource (lib "Schlib1") (part "CMP-2000-05026-1"))
    )
    (comp (ref "U167")
      (value "WS2812B")
      (footprint "LED5050")
      (fields (field (name "MANUFACTURER") "Adafruit-Industries-LLC") (field (name "LCSC PART #") "C114586"))
      (libsource (lib "Schlib1") (part "CMP-2000-05026-1"))
    )
    (comp (ref "U168")
      (value "WS2812B")
      (footprint "LED5050")
      (fields (field (name "MANUFACTURER") "Adafruit-Industries-LLC") (field (name "LCSC PART #") "C114586"))
      (libsource (lib "Schlib1") (part "CMP-2000-05026-1"))
    )
    (comp (ref "U169")
      (value "WS2812B")
      (footprint "LED5050")
      (fields (field (name "MANUFACTURER") "Adafruit-Industries-LLC") (field (name "LCSC PART #") "C114586"))
      (libsource (lib "Schlib1") (part "CMP-2000-05026-1"))
    )
    (comp (ref "U170")
      (value "WS2812B")
      (footprint "LED5050")
      (fields (field (name "MANUFACTURER") "Adafruit-Industries-LLC") (field (name "LCSC PART #") "C114586"))
      (libsource (lib "Schlib1") (part "CMP-2000-05026-1"))
    )
    (comp (ref "U171")
      (value "WS2812B")
      (footprint "LED5050")
      (fields (field (name "MANUFACTURER") "Adafruit-Industries-LLC") (field (name "LCSC PART #") "C114586"))
      (libsource (lib "Schlib1") (part "CMP-2000-05026-1"))
    )
    (comp (ref "U172")
      (value "WS2812B")
      (footprint "LED5050")
      (fields (field (name "MANUFACTURER") "Adafruit-Industries-LLC") (field (name "LCSC PART #") "C114586"))
      (libsource (lib "Schlib1") (part "CMP-2000-05026-1"))
    )
    (comp (ref "U173")
      (value "WS2812B")
      (footprint "LED5050")
      (fields (field (name "MANUFACTURER") "Adafruit-Industries-LLC") (field (name "LCSC PART #") "C114586"))
      (libsource (lib "Schlib1") (part "CMP-2000-05026-1"))
    )
    (comp (ref "U174")
      (value "WS2812B")
      (footprint "LED5050")
      (fields (field (name "MANUFACTURER") "Adafruit-Industries-LLC") (field (name "LCSC PART #") "C114586"))
      (libsource (lib "Schlib1") (part "CMP-2000-05026-1"))
    )
    (comp (ref "U175")
      (value "WS2812B")
      (footprint "LED5050")
      (fields (field (name "MANUFACTURER") "Adafruit-Industries-LLC") (field (name "LCSC PART #") "C114586"))
      (libsource (lib "Schlib1") (part "CMP-2000-05026-1"))
    )
    (comp (ref "U176")
      (value "WS2812B")
      (footprint "LED5050")
      (fields (field (name "MANUFACTURER") "Adafruit-Industries-LLC") (field (name "LCSC PART #") "C114586"))
      (libsource (lib "Schlib1") (part "CMP-2000-05026-1"))
    )
    (comp (ref "U177")
      (value "WS2812B")
      (footprint "LED5050")
      (fields (field (name "MANUFACTURER") "Adafruit-Industries-LLC") (field (name "LCSC PART #") "C114586"))
      (libsource (lib "Schlib1") (part "CMP-2000-05026-1"))
    )
    (comp (ref "U178")
      (value "WS2812B")
      (footprint "LED5050")
      (fields (field (name "MANUFACTURER") "Adafruit-Industries-LLC") (field (name "LCSC PART #") "C114586"))
      (libsource (lib "Schlib1") (part "CMP-2000-05026-1"))
    )
    (comp (ref "U179")
      (value "WS2812B")
      (footprint "LED5050")
      (fields (field (name "MANUFACTURER") "Adafruit-Industries-LLC") (field (name "LCSC PART #") "C114586"))
      (libsource (lib "Schlib1") (part "CMP-2000-05026-1"))
    )
    (comp (ref "U180")
      (value "WS2812B")
      (footprint "LED5050")
      (fields (field (name "MANUFACTURER") "Adafruit-Industries-LLC") (field (name "LCSC PART #") "C114586"))
      (libsource (lib "Schlib1") (part "CMP-2000-05026-1"))
    )
    (comp (ref "U181")
      (value "WS2812B")
      (footprint "LED5050")
      (fields (field (name "MANUFACTURER") "Adafruit-Industries-LLC") (field (name "LCSC PART #") "C114586"))
      (libsource (lib "Schlib1") (part "CMP-2000-05026-1"))
    )
    (comp (ref "U182")
      (value "WS2812B")
      (footprint "LED5050")
      (fields (field (name "MANUFACTURER") "Adafruit-Industries-LLC") (field (name "LCSC PART #") "C114586"))
      (libsource (lib "Schlib1") (part "CMP-2000-05026-1"))
    )
    (comp (ref "U183")
      (value "WS2812B")
      (footprint "LED5050")
      (fields (field (name "MANUFACTURER") "Adafruit-Industries-LLC") (field (name "LCSC PART #") "C114586"))
      (libsource (lib "Schlib1") (part "CMP-2000-05026-1"))
    )
    (comp (ref "U184")
      (value "WS2812B")
      (footprint "LED5050")
      (fields (field (name "MANUFACTURER") "Adafruit-Industries-LLC") (field (name "LCSC PART #") "C114586"))
      (libsource (lib "Schlib1") (part "CMP-2000-05026-1"))
    )
    (comp (ref "U185")
      (value "WS2812B")
      (footprint "LED5050")
      (fields (field (name "MANUFACTURER") "Adafruit-Industries-LLC") (field (name "LCSC PART #") "C114586"))
      (libsource (lib "Schlib1") (part "CMP-2000-05026-1"))
    )
    (comp (ref "U186")
      (value "WS2812B")
      (footprint "LED5050")
      (fields (field (name "MANUFACTURER") "Adafruit-Industries-LLC") (field (name "LCSC PART #") "C114586"))
      (libsource (lib "Schlib1") (part "CMP-2000-05026-1"))
    )
    (comp (ref "U187")
      (value "WS2812B")
      (footprint "LED5050")
      (fields (field (name "MANUFACTURER") "Adafruit-Industries-LLC") (field (name "LCSC PART #") "C114586"))
      (libsource (lib "Schlib1") (part "CMP-2000-05026-1"))
    )
    (comp (ref "U188")
      (value "WS2812B")
      (footprint "LED5050")
      (fields (field (name "MANUFACTURER") "Adafruit-Industries-LLC") (field (name "LCSC PART #") "C114586"))
      (libsource (lib "Schlib1") (part "CMP-2000-05026-1"))
    )
    (comp (ref "U189")
      (value "WS2812B")
      (footprint "LED5050")
      (fields (field (name "MANUFACTURER") "Adafruit-Industries-LLC") (field (name "LCSC PART #") "C114586"))
      (libsource (lib "Schlib1") (part "CMP-2000-05026-1"))
    )
    (comp (ref "U190")
      (value "WS2812B")
      (footprint "LED5050")
      (fields (field (name "MANUFACTURER") "Adafruit-Industries-LLC") (field (name "LCSC PART #") "C114586"))
      (libsource (lib "Schlib1") (part "CMP-2000-05026-1"))
    )
    (comp (ref "U191")
      (value "WS2812B")
      (footprint "LED5050")
      (fields (field (name "MANUFACTURER") "Adafruit-Industries-LLC") (field (name "LCSC PART #") "C114586"))
      (libsource (lib "Schlib1") (part "CMP-2000-05026-1"))
    )
    (comp (ref "U192")
      (value "WS2812B")
      (footprint "LED5050")
      (fields (field (name "MANUFACTURER") "Adafruit-Industries-LLC") (field (name "LCSC PART #") "C114586"))
      (libsource (lib "Schlib1") (part "CMP-2000-05026-1"))
    )
    (comp (ref "U193")
      (value "WS2812B")
      (footprint "LED5050")
      (fields (field (name "MANUFACTURER") "Adafruit-Industries-LLC") (field (name "LCSC PART #") "C114586"))
      (libsource (lib "Schlib1") (part "CMP-2000-05026-1"))
    )
    (comp (ref "U194")
      (value "WS2812B")
      (footprint "LED5050")
      (fields (field (name "MANUFACTURER") "Adafruit-Industries-LLC") (field (name "LCSC PART #") "C114586"))
      (libsource (lib "Schlib1") (part "CMP-2000-05026-1"))
    )
    (comp (ref "U195")
      (value "WS2812B")
      (footprint "LED5050")
      (fields (field (name "MANUFACTURER") "Adafruit-Industries-LLC") (field (name "LCSC PART #") "C114586"))
      (libsource (lib "Schlib1") (part "CMP-2000-05026-1"))
    )
    (comp (ref "U196")
      (value "WS2812B")
      (footprint "LED5050")
      (fields (field (name "MANUFACTURER") "Adafruit-Industries-LLC") (field (name "LCSC PART #") "C114586"))
      (libsource (lib "Schlib1") (part "CMP-2000-05026-1"))
    )
    (comp (ref "U197")
      (value "WS2812B")
      (footprint "LED5050")
      (fields (field (name "MANUFACTURER") "Adafruit-Industries-LLC") (field (name "LCSC PART #") "C114586"))
      (libsource (lib "Schlib1") (part "CMP-2000-05026-1"))
    )
    (comp (ref "U198")
      (value "WS2812B")
      (footprint "LED5050")
      (fields (field (name "MANUFACTURER") "Adafruit-Industries-LLC") (field (name "LCSC PART #") "C114586"))
      (libsource (lib "Schlib1") (part "CMP-2000-05026-1"))
    )
    (comp (ref "U199")
      (value "WS2812B")
      (footprint "LED5050")
      (fields (field (name "MANUFACTURER") "Adafruit-Industries-LLC") (field (name "LCSC PART #") "C114586"))
      (libsource (lib "Schlib1") (part "CMP-2000-05026-1"))
    )
    (comp (ref "U200")
      (value "WS2812B")
      (footprint "LED5050")
      (fields (field (name "MANUFACTURER") "Adafruit-Industries-LLC") (field (name "LCSC PART #") "C114586"))
      (libsource (lib "Schlib1") (part "CMP-2000-05026-1"))
    )
    (comp (ref "U201")
      (value "WS2812B")
      (footprint "LED5050")
      (fields (field (name "MANUFACTURER") "Adafruit-Industries-LLC") (field (name "LCSC PART #") "C114586"))
      (libsource (lib "Schlib1") (part "CMP-2000-05026-1"))
    )
    (comp (ref "U202")
      (value "WS2812B")
      (footprint "LED5050")
      (fields (field (name "MANUFACTURER") "Adafruit-Industries-LLC") (field (name "LCSC PART #") "C114586"))
      (libsource (lib "Schlib1") (part "CMP-2000-05026-1"))
    )
    (comp (ref "U203")
      (value "WS2812B")
      (footprint "LED5050")
      (fields (field (name "MANUFACTURER") "Adafruit-Industries-LLC") (field (name "LCSC PART #") "C114586"))
      (libsource (lib "Schlib1") (part "CMP-2000-05026-1"))
    )
    (comp (ref "U204")
      (value "WS2812B")
      (footprint "LED5050")
      (fields (field (name "MANUFACTURER") "Adafruit-Industries-LLC") (field (name "LCSC PART #") "C114586"))
      (libsource (lib "Schlib1") (part "CMP-2000-05026-1"))
    )
    (comp (ref "U205")
      (value "WS2812B")
      (footprint "LED5050")
      (fields (field (name "MANUFACTURER") "Adafruit-Industries-LLC") (field (name "LCSC PART #") "C114586"))
      (libsource (lib "Schlib1") (part "CMP-2000-05026-1"))
    )
    (comp (ref "U206")
      (value "WS2812B")
      (footprint "LED5050")
      (fields (field (name "MANUFACTURER") "Adafruit-Industries-LLC") (field (name "LCSC PART #") "C114586"))
      (libsource (lib "Schlib1") (part "CMP-2000-05026-1"))
    )
    (comp (ref "U207")
      (value "WS2812B")
      (footprint "LED5050")
      (fields (field (name "MANUFACTURER") "Adafruit-Industries-LLC") (field (name "LCSC PART #") "C114586"))
      (libsource (lib "Schlib1") (part "CMP-2000-05026-1"))
    )
    (comp (ref "U208")
      (value "WS2812B")
      (footprint "LED5050")
      (fields (field (name "MANUFACTURER") "Adafruit-Industries-LLC") (field (name "LCSC PART #") "C114586"))
      (libsource (lib "Schlib1") (part "CMP-2000-05026-1"))
    )
    (comp (ref "U209")
      (value "WS2812B")
      (footprint "LED5050")
      (fields (field (name "MANUFACTURER") "Adafruit-Industries-LLC") (field (name "LCSC PART #") "C114586"))
      (libsource (lib "Schlib1") (part "CMP-2000-05026-1"))
    )
    (comp (ref "U210")
      (value "WS2812B")
      (footprint "LED5050")
      (fields (field (name "MANUFACTURER") "Adafruit-Industries-LLC") (field (name "LCSC PART #") "C114586"))
      (libsource (lib "Schlib1") (part "CMP-2000-05026-1"))
    )
    (comp (ref "U211")
      (value "WS2812B")
      (footprint "LED5050")
      (fields (field (name "MANUFACTURER") "Adafruit-Industries-LLC") (field (name "LCSC PART #") "C114586"))
      (libsource (lib "Schlib1") (part "CMP-2000-05026-1"))
    )
    (comp (ref "U212")
      (value "WS2812B")
      (footprint "LED5050")
      (fields (field (name "MANUFACTURER") "Adafruit-Industries-LLC") (field (name "LCSC PART #") "C114586"))
      (libsource (lib "Schlib1") (part "CMP-2000-05026-1"))
    )
    (comp (ref "U213")
      (value "WS2812B")
      (footprint "LED5050")
      (fields (field (name "MANUFACTURER") "Adafruit-Industries-LLC") (field (name "LCSC PART #") "C114586"))
      (libsource (lib "Schlib1") (part "CMP-2000-05026-1"))
    )
    (comp (ref "U214")
      (value "WS2812B")
      (footprint "LED5050")
      (fields (field (name "MANUFACTURER") "Adafruit-Industries-LLC") (field (name "LCSC PART #") "C114586"))
      (libsource (lib "Schlib1") (part "CMP-2000-05026-1"))
    )
    (comp (ref "U215")
      (value "WS2812B")
      (footprint "LED5050")
      (fields (field (name "MANUFACTURER") "Adafruit-Industries-LLC") (field (name "LCSC PART #") "C114586"))
      (libsource (lib "Schlib1") (part "CMP-2000-05026-1"))
    )
    (comp (ref "U216")
      (value "WS2812B")
      (footprint "LED5050")
      (fields (field (name "MANUFACTURER") "Adafruit-Industries-LLC") (field (name "LCSC PART #") "C114586"))
      (libsource (lib "Schlib1") (part "CMP-2000-05026-1"))
    )
    (comp (ref "U217")
      (value "WS2812B")
      (footprint "LED5050")
      (fields (field (name "MANUFACTURER") "Adafruit-Industries-LLC") (field (name "LCSC PART #") "C114586"))
      (libsource (lib "Schlib1") (part "CMP-2000-05026-1"))
    )
    (comp (ref "U218")
      (value "WS2812B")
      (footprint "LED5050")
      (fields (field (name "MANUFACTURER") "Adafruit-Industries-LLC") (field (name "LCSC PART #") "C114586"))
      (libsource (lib "Schlib1") (part "CMP-2000-05026-1"))
    )
    (comp (ref "U219")
      (value "WS2812B")
      (footprint "LED5050")
      (fields (field (name "MANUFACTURER") "Adafruit-Industries-LLC") (field (name "LCSC PART #") "C114586"))
      (libsource (lib "Schlib1") (part "CMP-2000-05026-1"))
    )
    (comp (ref "U220")
      (value "WS2812B")
      (footprint "LED5050")
      (fields (field (name "MANUFACTURER") "Adafruit-Industries-LLC") (field (name "LCSC PART #") "C114586"))
      (libsource (lib "Schlib1") (part "CMP-2000-05026-1"))
    )
  )
  (nets
    (net (code "1") (name "/LED_SERIAL_0") (class "Default")
      (node (ref "U1") (pin "4") (pinfunction "DIN_4") (pintype "input"))
    )
    (net (code "2") (name "/LED_SERIAL_1") (class "Default")
      (node (ref "U41") (pin "4") (pinfunction "DIN_4") (pintype "input"))
    )
    (net (code "3") (name "/LED_SERIAL_2") (class "Default")
      (node (ref "U81") (pin "4") (pinfunction "DIN_4") (pintype "input"))
    )
    (net (code "4") (name "/LED_SERIAL_3") (class "Default")
      (node (ref "U121") (pin "4") (pinfunction "DIN_4") (pintype "input"))
    )
    (net (code "5") (name "/LED_SERIAL_4") (class "Default")
      (node (ref "U161") (pin "4") (pinfunction "DIN_4") (pintype "input"))
    )
    (net (code "6") (name "GND") (class "Default")
      (node (ref "U1") (pin "3") (pinfunction "VSS_3") (pintype "power_in"))
      (node (ref "U10") (pin "3") (pinfunction "VSS_3") (pintype "power_in"))
      (node (ref "U100") (pin "3") (pinfunction "VSS_3") (pintype "power_in"))
      (node (ref "U101") (pin "3") (pinfunction "VSS_3") (pintype "power_in"))
      (node (ref "U102") (pin "3") (pinfunction "VSS_3") (pintype "power_in"))
      (node (ref "U103") (pin "3") (pinfunction "VSS_3") (pintype "power_in"))
      (node (ref "U104") (pin "3") (pinfunction "VSS_3") (pintype "power_in"))
      (node (ref "U105") (pin "3") (pinfunction "VSS_3") (pintype "power_in"))
      (node (ref "U106") (pin "3") (pinfunction "VSS_3") (pintype "power_in"))
      (node (ref "U107") (pin "3") (pinfunction "VSS_3") (pintype "power_in"))
      (node (ref "U108") (pin "3") (pinfunction "VSS_3") (pintype "power_in"))
      (node (ref "U109") (pin "3") (pinfunction "VSS_3") (pintype "power_in"))
      (node (ref "U11") (pin "3") (pinfunction "VSS_3") (pintype "power_in"))
      (node (ref "U110") (pin "3") (pinfunction "VSS_3") (pintype "power_in"))
      (node (ref "U111") (pin "3") (pinfunction "VSS_3") (pintype "power_in"))
      (node (ref "U112") (pin "3") (pinfunction "VSS_3") (pintype "power_in"))
      (node (ref "U113") (pin "3") (pinfunction "VSS_3") (pintype "power_in"))
      (node (ref "U114") (pin "3") (pinfunction "VSS_3") (pintype "power_in"))
      (node (ref "U115") (pin "3") (pinfunction "VSS_3") (pintype "power_in"))
      (node (ref "U116") (pin "3") (pinfunction "VSS_3") (pintype "power_in"))
      (node (ref "U117") (pin "3") (pinfunction "VSS_3") (pintype "power_in"))
      (node (ref "U118") (pin "3") (pinfunction "VSS_3") (pintype "power_in"))
      (node (ref "U119") (pin "3") (pinfunction "VSS_3") (pintype "power_in"))
      (node (ref "U12") (pin "3") (pinfunction "VSS_3") (pintype "power_in"))
      (node (ref "U120") (pin "3") (pinfunction "VSS_3") (pintype "power_in"))
      (node (ref "U121") (pin "3") (pinfunction "VSS_3") (pintype "power_in"))
      (node (ref "U122") (pin "3") (pinfunction "VSS_3") (pintype "power_in"))
      (node (ref "U123") (pin "3") (pinfunction "VSS_3") (pintype "power_in"))
      (node (ref "U124") (pin "3") (pinfunction "VSS_3") (pintype "power_in"))
      (node (ref "U125") (pin "3") (pinfunction "VSS_3") (pintype "power_in"))
      (node (ref "U126") (pin "3") (pinfunction "VSS_3") (pintype "power_in"))
      (node (ref "U127") (pin "3") (pinfunction "VSS_3") (pintype "power_in"))
      (node (ref "U128") (pin "3") (pinfunction "VSS_3") (pintype "power_in"))
      (node (ref "U129") (pin "3") (pinfunction "VSS_3") (pintype "power_in"))
      (node (ref "U13") (pin "3") (pinfunction "VSS_3") (pintype "power_in"))
      (node (ref "U130") (pin "3") (pinfunction "VSS_3") (pintype "power_in"))
      (node (ref "U131") (pin "3") (pinfunction "VSS_3") (pintype "power_in"))
      (node (ref "U132") (pin "3") (pinfunction "VSS_3") (pintype "power_in"))
      (node (ref "U133") (pin "3") (pinfunction "VSS_3") (pintype "power_in"))
      (node (ref "U134") (pin "3") (pinfunction "VSS_3") (pintype "power_in"))
      (node (ref "U135") (pin "3") (pinfunction "VSS_3") (pintype "power_in"))
      (node (ref "U136") (pin "3") (pinfunction "VSS_3") (pintype "power_in"))
      (node (ref "U137") (pin "3") (pinfunction "VSS_3") (pintype "power_in"))
      (node (ref "U138") (pin "3") (pinfunction "VSS_3") (pintype "power_in"))
      (node (ref "U139") (pin "3") (pinfunction "VSS_3") (pintype "power_in"))
      (node (ref "U14") (pin "3") (pinfunction "VSS_3") (pintype "power_in"))
      (node (ref "U140") (pin "3") (pinfunction "VSS_3") (pintype "power_in"))
      (node (ref "U141") (pin "3") (pinfunction "VSS_3") (pintype "power_in"))
      (node (ref "U142") (pin "3") (pinfunction "VSS_3") (pintype "power_in"))
      (node (ref "U143") (pin "3") (pinfunction "VSS_3") (pintype "power_in"))
      (node (ref "U144") (pin "3") (pinfunction "VSS_3") (pintype "power_in"))
      (node (ref "U145") (pin "3") (pinfunction "VSS_3") (pintype "power_in"))
      (node (ref "U146") (pin "3") (pinfunction "VSS_3") (pintype "power_in"))
      (node (ref "U147") (pin "3") (pinfunction "VSS_3") (pintype "power_in"))
      (node (ref "U148") (pin "3") (pinfunction "VSS_3") (pintype "power_in"))
      (node (ref "U149") (pin "3") (pinfunction "VSS_3") (pintype "power_in"))
      (node (ref "U15") (pin "3") (pinfunction "VSS_3") (pintype "power_in"))
      (node (ref "U150") (pin "3") (pinfunction "VSS_3") (pintype "power_in"))
      (node (ref "U151") (pin "3") (pinfunction "VSS_3") (pintype "power_in"))
      (node (ref "U152") (pin "3") (pinfunction "VSS_3") (pintype "power_in"))
      (node (ref "U153") (pin "3") (pinfunction "VSS_3") (pintype "power_in"))
      (node (ref "U154") (pin "3") (pinfunction "VSS_3") (pintype "power_in"))
      (node (ref "U155") (pin "3") (pinfunction "VSS_3") (pintype "power_in"))
      (node (ref "U156") (pin "3") (pinfunction "VSS_3") (pintype "power_in"))
      (node (ref "U157") (pin "3") (pinfunction "VSS_3") (pintype "power_in"))
      (node (ref "U158") (pin "3") (pinfunction "VSS_3") (pintype "power_in"))
      (node (ref "U159") (pin "3") (pinfunction "VSS_3") (pintype "power_in"))
      (node (ref "U16") (pin "3") (pinfunction "VSS_3") (pintype "power_in"))
      (node (ref "U160") (pin "3") (pinfunction "VSS_3") (pintype "power_in"))
      (node (ref "U161") (pin "3") (pinfunction "VSS_3") (pintype "power_in"))
      (node (ref "U162") (pin "3") (pinfunction "VSS_3") (pintype "power_in"))
      (node (ref "U163") (pin "3") (pinfunction "VSS_3") (pintype "power_in"))
      (node (ref "U164") (pin "3") (pinfunction "VSS_3") (pintype "power_in"))
      (node (ref "U165") (pin "3") (pinfunction "VSS_3") (pintype "power_in"))
      (node (ref "U166") (pin "3") (pinfunction "VSS_3") (pintype "power_in"))
      (node (ref "U167") (pin "3") (pinfunction "VSS_3") (pintype "power_in"))
      (node (ref "U168") (pin "3") (pinfunction "VSS_3") (pintype "power_in"))
      (node (ref "U169") (pin "3") (pinfunction "VSS_3") (pintype "power_in"))
      (node (ref "U17") (pin "3") (pinfunction "VSS_3") (pintype "power_in"))
      (node (ref "U170") (pin "3") (pinfunction "VSS_3") (pintype "power_in"))
      (node (ref "U171") (pin "3") (pinfunction "VSS_3") (pintype "power_in"))
      (node (ref "U172") (pin "3") (pinfunction "VSS_3") (pintype "power_in"))
      (node (ref "U173") (pin "3") (pinfunction "VSS_3") (pintype "power_in"))
      (node (ref "U174") (pin "3") (pinfunction "VSS_3") (pintype "power_in"))
      (node (ref "U175") (pin "3") (pinfunction "VSS_3") (pintype "power_in"))
      (node (ref "U176") (pin "3") (pinfunction "VSS_3") (pintype "power_in"))
      (node (ref "U177") (pin "3") (pinfunction "VSS_3") (pintype "power_in"))
      (node (ref "U178") (pin "3") (pinfunction "VSS_3") (pintype "power_in"))
      (node (ref "U179") (pin "3") (pinfunction "VSS_3") (pintype "power_in"))
      (node (ref "U18") (pin "3") (pinfunction "VSS_3") (pintype "power_in"))
      (node (ref "U180") (pin "3") (pinfunction "VSS_3") (pintype "power_in"))
      (node (ref "U181") (pin "3") (pinfunction "VSS_3") (pintype "power_in"))
      (node (ref "U182") (pin "3") (pinfunction "VSS_3") (pintype "power_in"))
      (node (ref "U183") (pin "3") (pinfunction "VSS_3") (pintype "power_in"))
      (node (ref "U184") (pin "3") (pinfunction "VSS_3") (pintype "power_in"))
      (node (ref "U185") (pin "3") (pinfunction "VSS_3") (pintype "power_in"))
      (node (ref "U186") (pin "3") (pinfunction "VSS_3") (pintype "power_in"))
      (node (ref "U187") (pin "3") (pinfunction "VSS_3") (pintype "power_in"))
      (node (ref "U188") (pin "3") (pinfunction "VSS_3") (pintype "power_in"))
      (node (ref "U189") (pin "3") (pinfunction "VSS_3") (pintype "power_in"))
      (node (ref "U19") (pin "3") (pinfunction "VSS_3") (pintype "power_in"))
      (node (ref "U190") (pin "3") (pinfunction "VSS_3") (pintype "power_in"))
      (node (ref "U191") (pin "3") (pinfunction "VSS_3") (pintype "power_in"))
      (node (ref "U192") (pin "3") (pinfunction "VSS_3") (pintype "power_in"))
      (node (ref "U193") (pin "3") (pinfunction "VSS_3") (pintype "power_in"))
      (node (ref "U194") (pin "3") (pinfunction "VSS_3") (pintype "power_in"))
      (node (ref "U195") (pin "3") (pinfunction "VSS_3") (pintype "power_in"))
      (node (ref "U196") (pin "3") (pinfunction "VSS_3") (pintype "power_in"))
      (node (ref "U197") (pin "3") (pinfunction "VSS_3") (pintype "power_in"))
      (node (ref "U198") (pin "3") (pinfunction "VSS_3") (pintype "power_in"))
      (node (ref "U199") (pin "3") (pinfunction "VSS_3") (pintype "power_in"))
      (node (ref "U2") (pin "3") (pinfunction "VSS_3") (pintype "power_in"))
      (node (ref "U20") (pin "3") (pinfunction "VSS_3") (pintype "power_in"))
      (node (ref "U200") (pin "3") (pinfunction "VSS_3") (pintype "power_in"))
      (node (ref "U201") (pin "3") (pinfunction "VSS_3") (pintype "power_in"))
      (node (ref "U202") (pin "3") (pinfunction "VSS_3") (pintype "power_in"))
      (node (ref "U203") (pin "3") (pinfunction "VSS_3") (pintype "power_in"))
      (node (ref "U204") (pin "3") (pinfunction "VSS_3") (pintype "power_in"))
      (node (ref "U205") (pin "3") (pinfunction "VSS_3") (pintype "power_in"))
      (node (ref "U206") (pin "3") (pinfunction "VSS_3") (pintype "power_in"))
      (node (ref "U207") (pin "3") (pinfunction "VSS_3") (pintype "power_in"))
      (node (ref "U208") (pin "3") (pinfunction "VSS_3") (pintype "power_in"))
      (node (ref "U209") (pin "3") (pinfunction "VSS_3") (pintype "power_in"))
      (node (ref "U21") (pin "3") (pinfunction "VSS_3") (pintype "power_in"))
      (node (ref "U210") (pin "3") (pinfunction "VSS_3") (pintype "power_in"))
      (node (ref "U211") (pin "3") (pinfunction "VSS_3") (pintype "power_in"))
      (node (ref "U212") (pin "3") (pinfunction "VSS_3") (pintype "power_in"))
      (node (ref "U213") (pin "3") (pinfunction "VSS_3") (pintype "power_in"))
      (node (ref "U214") (pin "3") (pinfunction "VSS_3") (pintype "power_in"))
      (node (ref "U215") (pin "3") (pinfunction "VSS_3") (pintype "power_in"))
      (node (ref "U216") (pin "3") (pinfunction "VSS_3") (pintype "power_in"))
      (node (ref "U217") (pin "3") (pinfunction "VSS_3") (pintype "power_in"))
      (node (ref "U218") (pin "3") (pinfunction "VSS_3") (pintype "power_in"))
      (node (ref "U219") (pin "3") (pinfunction "VSS_3") (pintype "power_in"))
      (node (ref "U22") (pin "3") (pinfunction "VSS_3") (pintype "power_in"))
      (node (ref "U220") (pin "3") (pinfunction "VSS_3") (pintype "power_in"))
      (node (ref "U23") (pin "3") (pinfunction "VSS_3") (pintype "power_in"))
      (node (ref "U24") (pin "3") (pinfunction "VSS_3") (pintype "power_in"))
      (node (ref "U25") (pin "3") (pinfunction "VSS_3") (pintype "power_in"))
      (node (ref "U26") (pin "3") (pinfunction "VSS_3") (pintype "power_in"))
      (node (ref "U27") (pin "3") (pinfunction "VSS_3") (pintype "power_in"))
      (node (ref "U28") (pin "3") (pinfunction "VSS_3") (pintype "power_in"))
      (node (ref "U29") (pin "3") (pinfunction "VSS_3") (pintype "power_in"))
      (node (ref "U3") (pin "3") (pinfunction "VSS_3") (pintype "power_in"))
      (node (ref "U30") (pin "3") (pinfunction "VSS_3") (pintype "power_in"))
      (node (ref "U31") (pin "3") (pinfunction "VSS_3") (pintype "power_in"))
      (node (ref "U32") (pin "3") (pinfunction "VSS_3") (pintype "power_in"))
      (node (ref "U33") (pin "3") (pinfunction "VSS_3") (pintype "power_in"))
      (node (ref "U34") (pin "3") (pinfunction "VSS_3") (pintype "power_in"))
      (node (ref "U35") (pin "3") (pinfunction "VSS_3") (pintype "power_in"))
      (node (ref "U36") (pin "3") (pinfunction "VSS_3") (pintype "power_in"))
      (node (ref "U37") (pin "3") (pinfunction "VSS_3") (pintype "power_in"))
      (node (ref "U38") (pin "3") (pinfunction "VSS_3") (pintype "power_in"))
      (node (ref "U39") (pin "3") (pinfunction "VSS_3") (pintype "power_in"))
      (node (ref "U4") (pin "3") (pinfunction "VSS_3") (pintype "power_in"))
      (node (ref "U40") (pin "3") (pinfunction "VSS_3") (pintype "power_in"))
      (node (ref "U41") (pin "3") (pinfunction "VSS_3") (pintype "power_in"))
      (node (ref "U42") (pin "3") (pinfunction "VSS_3") (pintype "power_in"))
      (node (ref "U43") (pin "3") (pinfunction "VSS_3") (pintype "power_in"))
      (node (ref "U44") (pin "3") (pinfunction "VSS_3") (pintype "power_in"))
      (node (ref "U45") (pin "3") (pinfunction "VSS_3") (pintype "power_in"))
      (node (ref "U46") (pin "3") (pinfunction "VSS_3") (pintype "power_in"))
      (node (ref "U47") (pin "3") (pinfunction "VSS_3") (pintype "power_in"))
      (node (ref "U48") (pin "3") (pinfunction "VSS_3") (pintype "power_in"))
      (node (ref "U49") (pin "3") (pinfunction "VSS_3") (pintype "power_in"))
      (node (ref "U5") (pin "3") (pinfunction "VSS_3") (pintype "power_in"))
      (node (ref "U50") (pin "3") (pinfunction "VSS_3") (pintype "power_in"))
      (node (ref "U51") (pin "3") (pinfunction "VSS_3") (pintype "power_in"))
      (node (ref "U52") (pin "3") (pinfunction "VSS_3") (pintype "power_in"))
      (node (ref "U53") (pin "3") (pinfunction "VSS_3") (pintype "power_in"))
      (node (ref "U54") (pin "3") (pinfunction "VSS_3") (pintype "power_in"))
      (node (ref "U55") (pin "3") (pinfunction "VSS_3") (pintype "power_in"))
      (node (ref "U56") (pin "3") (pinfunction "VSS_3") (pintype "power_in"))
      (node (ref "U57") (pin "3") (pinfunction "VSS_3") (pintype "power_in"))
      (node (ref "U58") (pin "3") (pinfunction "VSS_3") (pintype "power_in"))
      (node (ref "U59") (pin "3") (pinfunction "VSS_3") (pintype "power_in"))
      (node (ref "U6") (pin "3") (pinfunction "VSS_3") (pintype "power_in"))
      (node (ref "U60") (pin "3") (pinfunction "VSS_3") (pintype "power_in"))
      (node (ref "U61") (pin "3") (pinfunction "VSS_3") (pintype "power_in"))
      (node (ref "U62") (pin "3") (pinfunction "VSS_3") (pintype "power_in"))
      (node (ref "U63") (pin "3") (pinfunction "VSS_3") (pintype "power_in"))
      (node (ref "U64") (pin "3") (pinfunction "VSS_3") (pintype "power_in"))
      (node (ref "U65") (pin "3") (pinfunction "VSS_3") (pintype "power_in"))
      (node (ref "U66") (pin "3") (pinfunction "VSS_3") (pintype "power_in"))
      (node (ref "U67") (pin "3") (pinfunction "VSS_3") (pintype "power_in"))
      (node (ref "U68") (pin "3") (pinfunction "VSS_3") (pintype "power_in"))
      (node (ref "U69") (pin "3") (pinfunction "VSS_3") (pintype "power_in"))
      (node (ref "U7") (pin "3") (pinfunction "VSS_3") (pintype "power_in"))
      (node (ref "U70") (pin "3") (pinfunction "VSS_3") (pintype "power_in"))
      (node (ref "U71") (pin "3") (pinfunction "VSS_3") (pintype "power_in"))
      (node (ref "U72") (pin "3") (pinfunction "VSS_3") (pintype "power_in"))
      (node (ref "U73") (pin "3") (pinfunction "VSS_3") (pintype "power_in"))
      (node (ref "U74") (pin "3") (pinfunction "VSS_3") (pintype "power_in"))
      (node (ref "U75") (pin "3") (pinfunction "VSS_3") (pintype "power_in"))
      (node (ref "U76") (pin "3") (pinfunction "VSS_3") (pintype "power_in"))
      (node (ref "U77") (pin "3") (pinfunction "VSS_3") (pintype "power_in"))
      (node (ref "U78") (pin "3") (pinfunction "VSS_3") (pintype "power_in"))
      (node (ref "U79") (pin "3") (pinfunction "VSS_3") (pintype "power_in"))
      (node (ref "U8") (pin "3") (pinfunction "VSS_3") (pintype "power_in"))
      (node (ref "U80") (pin "3") (pinfunction "VSS_3") (pintype "power_in"))
      (node (ref "U81") (pin "3") (pinfunction "VSS_3") (pintype "power_in"))
      (node (ref "U82") (pin "3") (pinfunction "VSS_3") (pintype "power_in"))
      (node (ref "U83") (pin "3") (pinfunction "VSS_3") (pintype "power_in"))
      (node (ref "U84") (pin "3") (pinfunction "VSS_3") (pintype "power_in"))
      (node (ref "U85") (pin "3") (pinfunction "VSS_3") (pintype "power_in"))
      (node (ref "U86") (pin "3") (pinfunction "VSS_3") (pintype "power_in"))
      (node (ref "U87") (pin "3") (pinfunction "VSS_3") (pintype "power_in"))
      (node (ref "U88") (pin "3") (pinfunction "VSS_3") (pintype "power_in"))
      (node (ref "U89") (pin "3") (pinfunction "VSS_3") (pintype "power_in"))
      (node (ref "U9") (pin "3") (pinfunction "VSS_3") (pintype "power_in"))
      (node (ref "U90") (pin "3") (pinfunction "VSS_3") (pintype "power_in"))
      (node (ref "U91") (pin "3") (pinfunction "VSS_3") (pintype "power_in"))
      (node (ref "U92") (pin "3") (pinfunction "VSS_3") (pintype "power_in"))
      (node (ref "U93") (pin "3") (pinfunction "VSS_3") (pintype "power_in"))
      (node (ref "U94") (pin "3") (pinfunction "VSS_3") (pintype "power_in"))
      (node (ref "U95") (pin "3") (pinfunction "VSS_3") (pintype "power_in"))
      (node (ref "U96") (pin "3") (pinfunction "VSS_3") (pintype "power_in"))
      (node (ref "U97") (pin "3") (pinfunction "VSS_3") (pintype "power_in"))
      (node (ref "U98") (pin "3") (pinfunction "VSS_3") (pintype "power_in"))
      (node (ref "U99") (pin "3") (pinfunction "VSS_3") (pintype "power_in"))
    )
    (net (code "7") (name "Net-(U1-DOUT)") (class "Default")
      (node (ref "U1") (pin "2") (pinfunction "DOUT_2") (pintype "output"))
      (node (ref "U2") (pin "4") (pinfunction "DIN_4") (pintype "input"))
    )
    (net (code "8") (name "Net-(U2-DOUT)") (class "Default")
      (node (ref "U2") (pin "2") (pinfunction "DOUT_2") (pintype "output"))
      (node (ref "U3") (pin "4") (pinfunction "DIN_4") (pintype "input"))
    )
    (net (code "9") (name "Net-(U3-DOUT)") (class "Default")
      (node (ref "U3") (pin "2") (pinfunction "DOUT_2") (pintype "output"))
      (node (ref "U4") (pin "4") (pinfunction "DIN_4") (pintype "input"))
    )
    (net (code "10") (name "Net-(U4-DOUT)") (class "Default")
      (node (ref "U4") (pin "2") (pinfunction "DOUT_2") (pintype "output"))
      (node (ref "U5") (pin "4") (pinfunction "DIN_4") (pintype "input"))
    )
    (net (code "11") (name "Net-(U5-DOUT)") (class "Default")
      (node (ref "U5") (pin "2") (pinfunction "DOUT_2") (pintype "output"))
      (node (ref "U6") (pin "4") (pinfunction "DIN_4") (pintype "input"))
    )
    (net (code "12") (name "Net-(U6-DOUT)") (class "Default")
      (node (ref "U6") (pin "2") (pinfunction "DOUT_2") (pintype "output"))
      (node (ref "U7") (pin "4") (pinfunction "DIN_4") (pintype "input"))
    )
    (net (code "13") (name "Net-(U7-DOUT)") (class "Default")
      (node (ref "U7") (pin "2") (pinfunction "DOUT_2") (pintype "output"))
      (node (ref "U8") (pin "4") (pinfunction "DIN_4") (pintype "input"))
    )
    (net (code "14") (name "Net-(U8-DOUT)") (class "Default")
      (node (ref "U8") (pin "2") (pinfunction "DOUT_2") (pintype "output"))
      (node (ref "U9") (pin "4") (pinfunction "DIN_4") (pintype "input"))
    )
    (net (code "15") (name "Net-(U10-DIN)") (class "Default")
      (node (ref "U10") (pin "4") (pinfunction "DIN_4") (pintype "input"))
      (node (ref "U9") (pin "2") (pinfunction "DOUT_2") (pintype "output"))
    )
    (net (code "16") (name "Net-(U10-DOUT)") (class "Default")
      (node (ref "U10") (pin "2") (pinfunction "DOUT_2") (pintype "output"))
      (node (ref "U11") (pin "4") (pinfunction "DIN_4") (pintype "input"))
    )
    (net (code "17") (name "Net-(U11-DOUT)") (class "Default")
      (node (ref "U11") (pin "2") (pinfunction "DOUT_2") (pintype "output"))
      (node (ref "U12") (pin "4") (pinfunction "DIN_4") (pintype "input"))
    )
    (net (code "18") (name "Net-(U12-DOUT)") (class "Default")
      (node (ref "U12") (pin "2") (pinfunction "DOUT_2") (pintype "output"))
      (node (ref "U13") (pin "4") (pinfunction "DIN_4") (pintype "input"))
    )
    (net (code "19") (name "Net-(U13-DOUT)") (class "Default")
      (node (ref "U13") (pin "2") (pinfunction "DOUT_2") (pintype "output"))
      (node (ref "U14") (pin "4") (pinfunction "DIN_4") (pintype "input"))
    )
    (net (code "20") (name "Net-(U14-DOUT)") (class "Default")
      (node (ref "U14") (pin "2") (pinfunction "DOUT_2") (pintype "output"))
      (node (ref "U15") (pin "4") (pinfunction "DIN_4") (pintype "input"))
    )
    (net (code "21") (name "Net-(U15-DOUT)") (class "Default")
      (node (ref "U15") (pin "2") (pinfunction "DOUT_2") (pintype "output"))
      (node (ref "U16") (pin "4") (pinfunction "DIN_4") (pintype "input"))
    )
    (net (code "22") (name "Net-(U16-DOUT)") (class "Default")
      (node (ref "U16") (pin "2") (pinfunction "DOUT_2") (pintype "output"))
      (node (ref "U17") (pin "4") (pinfunction "DIN_4") (pintype "input"))
    )
    (net (code "23") (name "Net-(U17-DOUT)") (class "Default")
      (node (ref "U17") (pin "2") (pinfunction "DOUT_2") (pintype "output"))
      (node (ref "U18") (pin "4") (pinfunction "DIN_4") (pintype "input"))
    )
    (net (code "24") (name "Net-(U18-DOUT)") (class "Default")
      (node (ref "U18") (pin "2") (pinfunction "DOUT_2") (pintype "output"))
      (node (ref "U19") (pin "4") (pinfunction "DIN_4") (pintype "input"))
    )
    (net (code "25") (name "Net-(U19-DOUT)") (class "Default")
      (node (ref "U19") (pin "2") (pinfunction "DOUT_2") (pintype "output"))
      (node (ref "U20") (pin "4") (pinfunction "DIN_4") (pintype "input"))
    )
    (net (code "26") (name "Net-(U20-DOUT)") (class "Default")
      (node (ref "U20") (pin "2") (pinfunction "DOUT_2") (pintype "output"))
      (node (ref "U21") (pin "4") (pinfunction "DIN_4") (pintype "input"))
    )
    (net (code "27") (name "Net-(U21-DOUT)") (class "Default")
      (node (ref "U21") (pin "2") (pinfunction "DOUT_2") (pintype "output"))
      (node (ref "U22") (pin "4") (pinfunction "DIN_4") (pintype "input"))
    )
    (net (code "28") (name "Net-(U22-DOUT)") (class "Default")
      (node (ref "U22") (pin "2") (pinfunction "DOUT_2") (pintype "output"))
      (node (ref "U23") (pin "4") (pinfunction "DIN_4") (pintype "input"))
    )
    (net (code "29") (name "Net-(U23-DOUT)") (class "Default")
      (node (ref "U23") (pin "2") (pinfunction "DOUT_2") (pintype "output"))
      (node (ref "U24") (pin "4") (pinfunction "DIN_4") (pintype "input"))
    )
    (net (code "30") (name "Net-(U24-DOUT)") (class "Default")
      (node (ref "U24") (pin "2") (pinfunction "DOUT_2") (pintype "output"))
      (node (ref "U25") (pin "4") (pinfunction "DIN_4") (pintype "input"))
    )
    (net (code "31") (name "Net-(U25-DOUT)") (class "Default")
      (node (ref "U25") (pin "2") (pinfunction "DOUT_2") (pintype "output"))
      (node (ref "U26") (pin "4") (pinfunction "DIN_4") (pintype "input"))
    )
    (net (code "32") (name "Net-(U26-DOUT)") (class "Default")
      (node (ref "U26") (pin "2") (pinfunction "DOUT_2") (pintype "output"))
      (node (ref "U27") (pin "4") (pinfunction "DIN_4") (pintype "input"))
    )
    (net (code "33") (name "Net-(U27-DOUT)") (class "Default")
      (node (ref "U27") (pin "2") (pinfunction "DOUT_2") (pintype "output"))
      (node (ref "U28") (pin "4") (pinfunction "DIN_4") (pintype "input"))
    )
    (net (code "34") (name "Net-(U28-DOUT)") (class "Default")
      (node (ref "U28") (pin "2") (pinfunction "DOUT_2") (pintype "output"))
      (node (ref "U29") (pin "4") (pinfunction "DIN_4") (pintype "input"))
    )
    (net (code "35") (name "Net-(U29-DOUT)") (class "Default")
      (node (ref "U29") (pin "2") (pinfunction "DOUT_2") (pintype "output"))
      (node (ref "U30") (pin "4") (pinfunction "DIN_4") (pintype "input"))
    )
    (net (code "36") (name "Net-(U30-DOUT)") (class "Default")
      (node (ref "U30") (pin "2") (pinfunction "DOUT_2") (pintype "output"))
      (node (ref "U31") (pin "4") (pinfunction "DIN_4") (pintype "input"))
    )
    (net (code "37") (name "Net-(U31-DOUT)") (class "Default")
      (node (ref "U31") (pin "2") (pinfunction "DOUT_2") (pintype "output"))
      (node (ref "U32") (pin "4") (pinfunction "DIN_4") (pintype "input"))
    )
    (net (code "38") (name "Net-(U32-DOUT)") (class "Default")
      (node (ref "U32") (pin "2") (pinfunction "DOUT_2") (pintype "output"))
      (node (ref "U33") (pin "4") (pinfunction "DIN_4") (pintype "input"))
    )
    (net (code "39") (name "Net-(U33-DOUT)") (class "Default")
      (node (ref "U33") (pin "2") (pinfunction "DOUT_2") (pintype "output"))
      (node (ref "U34") (pin "4") (pinfunction "DIN_4") (pintype "input"))
    )
    (net (code "40") (name "Net-(U34-DOUT)") (class "Default")
      (node (ref "U34") (pin "2") (pinfunction "DOUT_2") (pintype "output"))
      (node (ref "U35") (pin "4") (pinfunction "DIN_4") (pintype "input"))
    )
    (net (code "41") (name "Net-(U35-DOUT)") (class "Default")
      (node (ref "U35") (pin "2") (pinfunction "DOUT_2") (pintype "output"))
      (node (ref "U36") (pin "4") (pinfunction "DIN_4") (pintype "input"))
    )
    (net (code "42") (name "Net-(U36-DOUT)") (class "Default")
      (node (ref "U36") (pin "2") (pinfunction "DOUT_2") (pintype "output"))
      (node (ref "U37") (pin "4") (pinfunction "DIN_4") (pintype "input"))
    )
    (net (code "43") (name "Net-(U37-DOUT)") (class "Default")
      (node (ref "U37") (pin "2") (pinfunction "DOUT_2") (pintype "output"))
      (node (ref "U38") (pin "4") (pinfunction "DIN_4") (pintype "input"))
    )
    (net (code "44") (name "Net-(U38-DOUT)") (class "Default")
      (node (ref "U38") (pin "2") (pinfunction "DOUT_2") (pintype "output"))
      (node (ref "U39") (pin "4") (pinfunction "DIN_4") (pintype "input"))
    )
    (net (code "45") (name "Net-(U39-DOUT)") (class "Default")
      (node (ref "U39") (pin "2") (pinfunction "DOUT_2") (pintype "output"))
      (node (ref "U40") (pin "4") (pinfunction "DIN_4") (pintype "input"))
    )
    (net (code "46") (name "Net-(U41-DOUT)") (class "Default")
      (node (ref "U41") (pin "2") (pinfunction "DOUT_2") (pintype "output"))
      (node (ref "U42") (pin "4") (pinfunction "DIN_4") (pintype "input"))
    )
    (net (code "47") (name "Net-(U42-DOUT)") (class "Default")
      (node (ref "U42") (pin "2") (pinfunction "DOUT_2") (pintype "output"))
      (node (ref "U43") (pin "4") (pinfunction "DIN_4") (pintype "input"))
    )
    (net (code "48") (name "Net-(U43-DOUT)") (class "Default")
      (node (ref "U43") (pin "2") (pinfunction "DOUT_2") (pintype "output"))
      (node (ref "U44") (pin "4") (pinfunction "DIN_4") (pintype "input"))
    )
    (net (code "49") (name "Net-(U44-DOUT)") (class "Default")
      (node (ref "U44") (pin "2") (pinfunction "DOUT_2") (pintype "output"))
      (node (ref "U45") (pin "4") (pinfunction "DIN_4") (pintype "input"))
    )
    (net (code "50") (name "Net-(U45-DOUT)") (class "Default")
      (node (ref "U45") (pin "2") (pinfunction "DOUT_2") (pintype "output"))
      (node (ref "U46") (pin "4") (pinfunction "DIN_4") (pintype "input"))
    )
    (net (code "51") (name "Net-(U46-DOUT)") (class "Default")
      (node (ref "U46") (pin "2") (pinfunction "DOUT_2") (pintype "output"))
      (node (ref "U47") (pin "4") (pinfunction "DIN_4") (pintype "input"))
    )
    (net (code "52") (name "Net-(U47-DOUT)") (class "Default")
      (node (ref "U47") (pin "2") (pinfunction "DOUT_2") (pintype "output"))
      (node (ref "U48") (pin "4") (pinfunction "DIN_4") (pintype "input"))
    )
    (net (code "53") (name "Net-(U48-DOUT)") (class "Default")
      (node (ref "U48") (pin "2") (pinfunction "DOUT_2") (pintype "output"))
      (node (ref "U49") (pin "4") (pinfunction "DIN_4") (pintype "input"))
    )
    (net (code "54") (name "Net-(U49-DOUT)") (class "Default")
      (node (ref "U49") (pin "2") (pinfunction "DOUT_2") (pintype "output"))
      (node (ref "U50") (pin "4") (pinfunction "DIN_4") (pintype "input"))
    )
    (net (code "55") (name "Net-(U50-DOUT)") (class "Default")
      (node (ref "U50") (pin "2") (pinfunction "DOUT_2") (pintype "output"))
      (node (ref "U51") (pin "4") (pinfunction "DIN_4") (pintype "input"))
    )
    (net (code "56") (name "Net-(U51-DOUT)") (class "Default")
      (node (ref "U51") (pin "2") (pinfunction "DOUT_2") (pintype "output"))
      (node (ref "U52") (pin "4") (pinfunction "DIN_4") (pintype "input"))
    )
    (net (code "57") (name "Net-(U52-DOUT)") (class "Default")
      (node (ref "U52") (pin "2") (pinfunction "DOUT_2") (pintype "output"))
      (node (ref "U53") (pin "4") (pinfunction "DIN_4") (pintype "input"))
    )
    (net (code "58") (name "Net-(U53-DOUT)") (class "Default")
      (node (ref "U53") (pin "2") (pinfunction "DOUT_2") (pintype "output"))
      (node (ref "U54") (pin "4") (pinfunction "DIN_4") (pintype "input"))
    )
    (net (code "59") (name "Net-(U54-DOUT)") (class "Default")
      (node (ref "U54") (pin "2") (pinfunction "DOUT_2") (pintype "output"))
      (node (ref "U55") (pin "4") (pinfunction "DIN_4") (pintype "input"))
    )
    (net (code "60") (name "Net-(U55-DOUT)") (class "Default")
      (node (ref "U55") (pin "2") (pinfunction "DOUT_2") (pintype "output"))
      (node (ref "U56") (pin "4") (pinfunction "DIN_4") (pintype "input"))
    )
    (net (code "61") (name "Net-(U56-DOUT)") (class "Default")
      (node (ref "U56") (pin "2") (pinfunction "DOUT_2") (pintype "output"))
      (node (ref "U57") (pin "4") (pinfunction "DIN_4") (pintype "input"))
    )
    (net (code "62") (name "Net-(U57-DOUT)") (class "Default")
      (node (ref "U57") (pin "2") (pinfunction "DOUT_2") (pintype "output"))
      (node (ref "U58") (pin "4") (pinfunction "DIN_4") (pintype "input"))
    )
    (net (code "63") (name "Net-(U58-DOUT)") (class "Default")
      (node (ref "U58") (pin "2") (pinfunction "DOUT_2") (pintype "output"))
      (node (ref "U59") (pin "4") (pinfunction "DIN_4") (pintype "input"))
    )
    (net (code "64") (name "Net-(U59-DOUT)") (class "Default")
      (node (ref "U59") (pin "2") (pinfunction "DOUT_2") (pintype "output"))
      (node (ref "U60") (pin "4") (pinfunction "DIN_4") (pintype "input"))
    )
    (net (code "65") (name "Net-(U60-DOUT)") (class "Default")
      (node (ref "U60") (pin "2") (pinfunction "DOUT_2") (pintype "output"))
      (node (ref "U61") (pin "4") (pinfunction "DIN_4") (pintype "input"))
    )
    (net (code "66") (name "Net-(U61-DOUT)") (class "Default")
      (node (ref "U61") (pin "2") (pinfunction "DOUT_2") (pintype "output"))
      (node (ref "U62") (pin "4") (pinfunction "DIN_4") (pintype "input"))
    )
    (net (code "67") (name "Net-(U62-DOUT)") (class "Default")
      (node (ref "U62") (pin "2") (pinfunction "DOUT_2") (pintype "output"))
      (node (ref "U63") (pin "4") (pinfunction "DIN_4") (pintype "input"))
    )
    (net (code "68") (name "Net-(U63-DOUT)") (class "Default")
      (node (ref "U63") (pin "2") (pinfunction "DOUT_2") (pintype "output"))
      (node (ref "U64") (pin "4") (pinfunction "DIN_4") (pintype "input"))
    )
    (net (code "69") (name "Net-(U64-DOUT)") (class "Default")
      (node (ref "U64") (pin "2") (pinfunction "DOUT_2") (pintype "output"))
      (node (ref "U65") (pin "4") (pinfunction "DIN_4") (pintype "input"))
    )
    (net (code "70") (name "Net-(U65-DOUT)") (class "Default")
      (node (ref "U65") (pin "2") (pinfunction "DOUT_2") (pintype "output"))
      (node (ref "U66") (pin "4") (pinfunction "DIN_4") (pintype "input"))
    )
    (net (code "71") (name "Net-(U66-DOUT)") (class "Default")
      (node (ref "U66") (pin "2") (pinfunction "DOUT_2") (pintype "output"))
      (node (ref "U67") (pin "4") (pinfunction "DIN_4") (pintype "input"))
    )
    (net (code "72") (name "Net-(U67-DOUT)") (class "Default")
      (node (ref "U67") (pin "2") (pinfunction "DOUT_2") (pintype "output"))
      (node (ref "U68") (pin "4") (pinfunction "DIN_4") (pintype "input"))
    )
    (net (code "73") (name "Net-(U68-DOUT)") (class "Default")
      (node (ref "U68") (pin "2") (pinfunction "DOUT_2") (pintype "output"))
      (node (ref "U69") (pin "4") (pinfunction "DIN_4") (pintype "input"))
    )
    (net (code "74") (name "Net-(U69-DOUT)") (class "Default")
      (node (ref "U69") (pin "2") (pinfunction "DOUT_2") (pintype "output"))
      (node (ref "U70") (pin "4") (pinfunction "DIN_4") (pintype "input"))
    )
    (net (code "75") (name "Net-(U70-DOUT)") (class "Default")
      (node (ref "U70") (pin "2") (pinfunction "DOUT_2") (pintype "output"))
      (node (ref "U71") (pin "4") (pinfunction "DIN_4") (pintype "input"))
    )
    (net (code "76") (name "Net-(U71-DOUT)") (class "Default")
      (node (ref "U71") (pin "2") (pinfunction "DOUT_2") (pintype "output"))
      (node (ref "U72") (pin "4") (pinfunction "DIN_4") (pintype "input"))
    )
    (net (code "77") (name "Net-(U72-DOUT)") (class "Default")
      (node (ref "U72") (pin "2") (pinfunction "DOUT_2") (pintype "output"))
      (node (ref "U73") (pin "4") (pinfunction "DIN_4") (pintype "input"))
    )
    (net (code "78") (name "Net-(U73-DOUT)") (class "Default")
      (node (ref "U73") (pin "2") (pinfunction "DOUT_2") (pintype "output"))
      (node (ref "U74") (pin "4") (pinfunction "DIN_4") (pintype "input"))
    )
    (net (code "79") (name "Net-(U74-DOUT)") (class "Default")
      (node (ref "U74") (pin "2") (pinfunction "DOUT_2") (pintype "output"))
      (node (ref "U75") (pin "4") (pinfunction "DIN_4") (pintype "input"))
    )
    (net (code "80") (name "Net-(U75-DOUT)") (class "Default")
      (node (ref "U75") (pin "2") (pinfunction "DOUT_2") (pintype "output"))
      (node (ref "U76") (pin "4") (pinfunction "DIN_4") (pintype "input"))
    )
    (net (code "81") (name "Net-(U76-DOUT)") (class "Default")
      (node (ref "U76") (pin "2") (pinfunction "DOUT_2") (pintype "output"))
      (node (ref "U77") (pin "4") (pinfunction "DIN_4") (pintype "input"))
    )
    (net (code "82") (name "Net-(U77-DOUT)") (class "Default")
      (node (ref "U77") (pin "2") (pinfunction "DOUT_2") (pintype "output"))
      (node (ref "U78") (pin "4") (pinfunction "DIN_4") (pintype "input"))
    )
    (net (code "83") (name "Net-(U78-DOUT)") (class "Default")
      (node (ref "U78") (pin "2") (pinfunction "DOUT_2") (pintype "output"))
      (node (ref "U79") (pin "4") (pinfunction "DIN_4") (pintype "input"))
    )
    (net (code "84") (name "Net-(U79-DOUT)") (class "Default")
      (node (ref "U79") (pin "2") (pinfunction "DOUT_2") (pintype "output"))
      (node (ref "U80") (pin "4") (pinfunction "DIN_4") (pintype "input"))
    )
    (net (code "85") (name "Net-(U81-DOUT)") (class "Default")
      (node (ref "U81") (pin "2") (pinfunction "DOUT_2") (pintype "output"))
      (node (ref "U82") (pin "4") (pinfunction "DIN_4") (pintype "input"))
    )
    (net (code "86") (name "Net-(U82-DOUT)") (class "Default")
      (node (ref "U82") (pin "2") (pinfunction "DOUT_2") (pintype "output"))
      (node (ref "U83") (pin "4") (pinfunction "DIN_4") (pintype "input"))
    )
    (net (code "87") (name "Net-(U83-DOUT)") (class "Default")
      (node (ref "U83") (pin "2") (pinfunction "DOUT_2") (pintype "output"))
      (node (ref "U84") (pin "4") (pinfunction "DIN_4") (pintype "input"))
    )
    (net (code "88") (name "Net-(U84-DOUT)") (class "Default")
      (node (ref "U84") (pin "2") (pinfunction "DOUT_2") (pintype "output"))
      (node (ref "U85") (pin "4") (pinfunction "DIN_4") (pintype "input"))
    )
    (net (code "89") (name "Net-(U85-DOUT)") (class "Default")
      (node (ref "U85") (pin "2") (pinfunction "DOUT_2") (pintype "output"))
      (node (ref "U86") (pin "4") (pinfunction "DIN_4") (pintype "input"))
    )
    (net (code "90") (name "Net-(U86-DOUT)") (class "Default")
      (node (ref "U86") (pin "2") (pinfunction "DOUT_2") (pintype "output"))
      (node (ref "U87") (pin "4") (pinfunction "DIN_4") (pintype "input"))
    )
    (net (code "91") (name "Net-(U87-DOUT)") (class "Default")
      (node (ref "U87") (pin "2") (pinfunction "DOUT_2") (pintype "output"))
      (node (ref "U88") (pin "4") (pinfunction "DIN_4") (pintype "input"))
    )
    (net (code "92") (name "Net-(U88-DOUT)") (class "Default")
      (node (ref "U88") (pin "2") (pinfunction "DOUT_2") (pintype "output"))
      (node (ref "U89") (pin "4") (pinfunction "DIN_4") (pintype "input"))
    )
    (net (code "93") (name "Net-(U89-DOUT)") (class "Default")
      (node (ref "U89") (pin "2") (pinfunction "DOUT_2") (pintype "output"))
      (node (ref "U90") (pin "4") (pinfunction "DIN_4") (pintype "input"))
    )
    (net (code "94") (name "Net-(U90-DOUT)") (class "Default")
      (node (ref "U90") (pin "2") (pinfunction "DOUT_2") (pintype "output"))
      (node (ref "U91") (pin "4") (pinfunction "DIN_4") (pintype "input"))
    )
    (net (code "95") (name "Net-(U91-DOUT)") (class "Default")
      (node (ref "U91") (pin "2") (pinfunction "DOUT_2") (pintype "output"))
      (node (ref "U92") (pin "4") (pinfunction "DIN_4") (pintype "input"))
    )
    (net (code "96") (name "Net-(U92-DOUT)") (class "Default")
      (node (ref "U92") (pin "2") (pinfunction "DOUT_2") (pintype "output"))
      (node (ref "U93") (pin "4") (pinfunction "DIN_4") (pintype "input"))
    )
    (net (code "97") (name "Net-(U93-DOUT)") (class "Default")
      (node (ref "U93") (pin "2") (pinfunction "DOUT_2") (pintype "output"))
      (node (ref "U94") (pin "4") (pinfunction "DIN_4") (pintype "input"))
    )
    (net (code "98") (name "Net-(U94-DOUT)") (class "Default")
      (node (ref "U94") (pin "2") (pinfunction "DOUT_2") (pintype "output"))
      (node (ref "U95") (pin "4") (pinfunction "DIN_4") (pintype "input"))
    )
    (net (code "99") (name "Net-(U95-DOUT)") (class "Default")
      (node (ref "U95") (pin "2") (pinfunction "DOUT_2") (pintype "output"))
      (node (ref "U96") (pin "4") (pinfunction "DIN_4") (pintype "input"))
    )
    (net (code "100") (name "Net-(U96-DOUT)") (class "Default")
      (node (ref "U96") (pin "2") (pinfunction "DOUT_2") (pintype "output"))
      (node (ref "U97") (pin "4") (pinfunction "DIN_4") (pintype "input"))
    )
    (net (code "101") (name "Net-(U97-DOUT)") (class "Default")
      (node (ref "U97") (pin "2") (pinfunction "DOUT_2") (pintype "output"))
      (node (ref "U98") (pin "4") (pinfunction "DIN_4") (pintype "input"))
    )
    (net (code "102") (name "Net-(U98-DOUT)") (class "Default")
      (node (ref "U98") (pin "2") (pinfunction "DOUT_2") (pintype "output"))
      (node (ref "U99") (pin "4") (pinfunction "DIN_4") (pintype "input"))
    )
    (net (code "103") (name "Net-(U100-DIN)") (class "Default")
      (node (ref "U100") (pin "4") (pinfunction "DIN_4") (pintype "input"))
      (node (ref "U99") (pin "2") (pinfunction "DOUT_2") (pintype "output"))
    )
    (net (code "104") (name "Net-(U100-DOUT)") (class "Default")
      (node (ref "U100") (pin "2") (pinfunction "DOUT_2") (pintype "output"))
      (node (ref "U101") (pin "4") (pinfunction "DIN_4") (pintype "input"))
    )
    (net (code "105") (name "Net-(U101-DOUT)") (class "Default")
      (node (ref "U101") (pin "2") (pinfunction "DOUT_2") (pintype "output"))
      (node (ref "U102") (pin "4") (pinfunction "DIN_4") (pintype "input"))
    )
    (net (code "106") (name "Net-(U102-DOUT)") (class "Default")
      (node (ref "U102") (pin "2") (pinfunction "DOUT_2") (pintype "output"))
      (node (ref "U103") (pin "4") (pinfunction "DIN_4") (pintype "input"))
    )
    (net (code "107") (name "Net-(U103-DOUT)") (class "Default")
      (node (ref "U103") (pin "2") (pinfunction "DOUT_2") (pintype "output"))
      (node (ref "U104") (pin "4") (pinfunction "DIN_4") (pintype "input"))
    )
    (net (code "108") (name "Net-(U104-DOUT)") (class "Default")
      (node (ref "U104") (pin "2") (pinfunction "DOUT_2") (pintype "output"))
      (node (ref "U105") (pin "4") (pinfunction "DIN_4") (pintype "input"))
    )
    (net (code "109") (name "Net-(U105-DOUT)") (class "Default")
      (node (ref "U105") (pin "2") (pinfunction "DOUT_2") (pintype "output"))
      (node (ref "U106") (pin "4") (pinfunction "DIN_4") (pintype "input"))
    )
    (net (code "110") (name "Net-(U106-DOUT)") (class "Default")
      (node (ref "U106") (pin "2") (pinfunction "DOUT_2") (pintype "output"))
      (node (ref "U107") (pin "4") (pinfunction "DIN_4") (pintype "input"))
    )
    (net (code "111") (name "Net-(U107-DOUT)") (class "Default")
      (node (ref "U107") (pin "2") (pinfunction "DOUT_2") (pintype "output"))
      (node (ref "U108") (pin "4") (pinfunction "DIN_4") (pintype "input"))
    )
    (net (code "112") (name "Net-(U108-DOUT)") (class "Default")
      (node (ref "U108") (pin "2") (pinfunction "DOUT_2") (pintype "output"))
      (node (ref "U109") (pin "4") (pinfunction "DIN_4") (pintype "input"))
    )
    (net (code "113") (name "Net-(U109-DOUT)") (class "Default")
      (node (ref "U109") (pin "2") (pinfunction "DOUT_2") (pintype "output"))
      (node (ref "U110") (pin "4") (pinfunction "DIN_4") (pintype "input"))
    )
    (net (code "114") (name "Net-(U110-DOUT)") (class "Default")
      (node (ref "U110") (pin "2") (pinfunction "DOUT_2") (pintype "output"))
      (node (ref "U111") (pin "4") (pinfunction "DIN_4") (pintype "input"))
    )
    (net (code "115") (name "Net-(U111-DOUT)") (class "Default")
      (node (ref "U111") (pin "2") (pinfunction "DOUT_2") (pintype "output"))
      (node (ref "U112") (pin "4") (pinfunction "DIN_4") (pintype "input"))
    )
    (net (code "116") (name "Net-(U112-DOUT)") (class "Default")
      (node (ref "U112") (pin "2") (pinfunction "DOUT_2") (pintype "output"))
      (node (ref "U113") (pin "4") (pinfunction "DIN_4") (pintype "input"))
    )
    (net (code "117") (name "Net-(U113-DOUT)") (class "Default")
      (node (ref "U113") (pin "2") (pinfunction "DOUT_2") (pintype "output"))
      (node (ref "U114") (pin "4") (pinfunction "DIN_4") (pintype "input"))
    )
    (net (code "118") (name "Net-(U114-DOUT)") (class "Default")
      (node (ref "U114") (pin "2") (pinfunction "DOUT_2") (pintype "output"))
      (node (ref "U115") (pin "4") (pinfunction "DIN_4") (pintype "input"))
    )
    (net (code "119") (name "Net-(U115-DOUT)") (class "Default")
      (node (ref "U115") (pin "2") (pinfunction "DOUT_2") (pintype "output"))
      (node (ref "U116") (pin "4") (pinfunction "DIN_4") (pintype "input"))
    )
    (net (code "120") (name "Net-(U116-DOUT)") (class "Default")
      (node (ref "U116") (pin "2") (pinfunction "DOUT_2") (pintype "output"))
      (node (ref "U117") (pin "4") (pinfunction "DIN_4") (pintype "input"))
    )
    (net (code "121") (name "Net-(U117-DOUT)") (class "Default")
      (node (ref "U117") (pin "2") (pinfunction "DOUT_2") (pintype "output"))
      (node (ref "U118") (pin "4") (pinfunction "DIN_4") (pintype "input"))
    )
    (net (code "122") (name "Net-(U118-DOUT)") (class "Default")
      (node (ref "U118") (pin "2") (pinfunction "DOUT_2") (pintype "output"))
      (node (ref "U119") (pin "4") (pinfunction "DIN_4") (pintype "input"))
    )
    (net (code "123") (name "Net-(U119-DOUT)") (class "Default")
      (node (ref "U119") (pin "2") (pinfunction "DOUT_2") (pintype "output"))
      (node (ref "U120") (pin "4") (pinfunction "DIN_4") (pintype "input"))
    )
    (net (code "124") (name "Net-(U121-DOUT)") (class "Default")
      (node (ref "U121") (pin "2") (pinfunction "DOUT_2") (pintype "output"))
      (node (ref "U122") (pin "4") (pinfunction "DIN_4") (pintype "input"))
    )
    (net (code "125") (name "Net-(U122-DOUT)") (class "Default")
      (node (ref "U122") (pin "2") (pinfunction "DOUT_2") (pintype "output"))
      (node (ref "U123") (pin "4") (pinfunction "DIN_4") (pintype "input"))
    )
    (net (code "126") (name "Net-(U123-DOUT)") (class "Default")
      (node (ref "U123") (pin "2") (pinfunction "DOUT_2") (pintype "output"))
      (node (ref "U124") (pin "4") (pinfunction "DIN_4") (pintype "input"))
    )
    (net (code "127") (name "Net-(U124-DOUT)") (class "Default")
      (node (ref "U124") (pin "2") (pinfunction "DOUT_2") (pintype "output"))
      (node (ref "U125") (pin "4") (pinfunction "DIN_4") (pintype "input"))
    )
    (net (code "128") (name "Net-(U125-DOUT)") (class "Default")
      (node (ref "U125") (pin "2") (pinfunction "DOUT_2") (pintype "output"))
      (node (ref "U126") (pin "4") (pinfunction "DIN_4") (pintype "input"))
    )
    (net (code "129") (name "Net-(U126-DOUT)") (class "Default")
      (node (ref "U126") (pin "2") (pinfunction "DOUT_2") (pintype "output"))
      (node (ref "U127") (pin "4") (pinfunction "DIN_4") (pintype "input"))
    )
    (net (code "130") (name "Net-(U127-DOUT)") (class "Default")
      (node (ref "U127") (pin "2") (pinfunction "DOUT_2") (pintype "output"))
      (node (ref "U128") (pin "4") (pinfunction "DIN_4") (pintype "input"))
    )
    (net (code "131") (name "Net-(U128-DOUT)") (class "Default")
      (node (ref "U128") (pin "2") (pinfunction "DOUT_2") (pintype "output"))
      (node (ref "U129") (pin "4") (pinfunction "DIN_4") (pintype "input"))
    )
    (net (code "132") (name "Net-(U129-DOUT)") (class "Default")
      (node (ref "U129") (pin "2") (pinfunction "DOUT_2") (pintype "output"))
      (node (ref "U130") (pin "4") (pinfunction "DIN_4") (pintype "input"))
    )
    (net (code "133") (name "Net-(U130-DOUT)") (class "Default")
      (node (ref "U130") (pin "2") (pinfunction "DOUT_2") (pintype "output"))
      (node (ref "U131") (pin "4") (pinfunction "DIN_4") (pintype "input"))
    )
    (net (code "134") (name "Net-(U131-DOUT)") (class "Default")
      (node (ref "U131") (pin "2") (pinfunction "DOUT_2") (pintype "output"))
      (node (ref "U132") (pin "4") (pinfunction "DIN_4") (pintype "input"))
    )
    (net (code "135") (name "Net-(U132-DOUT)") (class "Default")
      (node (ref "U132") (pin "2") (pinfunction "DOUT_2") (pintype "output"))
      (node (ref "U133") (pin "4") (pinfunction "DIN_4") (pintype "input"))
    )
    (net (code "136") (name "Net-(U133-DOUT)") (class "Default")
      (node (ref "U133") (pin "2") (pinfunction "DOUT_2") (pintype "output"))
      (node (ref "U134") (pin "4") (pinfunction "DIN_4") (pintype "input"))
    )
    (net (code "137") (name "Net-(U134-DOUT)") (class "Default")
      (node (ref "U134") (pin "2") (pinfunction "DOUT_2") (pintype "output"))
      (node (ref "U135") (pin "4") (pinfunction "DIN_4") (pintype "input"))
    )
    (net (code "138") (name "Net-(U135-DOUT)") (class "Default")
      (node (ref "U135") (pin "2") (pinfunction "DOUT_2") (pintype "output"))
      (node (ref "U136") (pin "4") (pinfunction "DIN_4") (pintype "input"))
    )
    (net (code "139") (name "Net-(U136-DOUT)") (class "Default")
      (node (ref "U136") (pin "2") (pinfunction "DOUT_2") (pintype "output"))
      (node (ref "U137") (pin "4") (pinfunction "DIN_4") (pintype "input"))
    )
    (net (code "140") (name "Net-(U137-DOUT)") (class "Default")
      (node (ref "U137") (pin "2") (pinfunction "DOUT_2") (pintype "output"))
      (node (ref "U138") (pin "4") (pinfunction "DIN_4") (pintype "input"))
    )
    (net (code "141") (name "Net-(U138-DOUT)") (class "Default")
      (node (ref "U138") (pin "2") (pinfunction "DOUT_2") (pintype "output"))
      (node (ref "U139") (pin "4") (pinfunction "DIN_4") (pintype "input"))
    )
    (net (code "142") (name "Net-(U139-DOUT)") (class "Default")
      (node (ref "U139") (pin "2") (pinfunction "DOUT_2") (pintype "output"))
      (node (ref "U140") (pin "4") (pinfunction "DIN_4") (pintype "input"))
    )
    (net (code "143") (name "Net-(U140-DOUT)") (class "Default")
      (node (ref "U140") (pin "2") (pinfunction "DOUT_2") (pintype "output"))
      (node (ref "U141") (pin "4") (pinfunction "DIN_4") (pintype "input"))
    )
    (net (code "144") (name "Net-(U141-DOUT)") (class "Default")
      (node (ref "U141") (pin "2") (pinfunction "DOUT_2") (pintype "output"))
      (node (ref "U142") (pin "4") (pinfunction "DIN_4") (pintype "input"))
    )
    (net (code "145") (name "Net-(U142-DOUT)") (class "Default")
      (node (ref "U142") (pin "2") (pinfunction "DOUT_2") (pintype "output"))
      (node (ref "U143") (pin "4") (pinfunction "DIN_4") (pintype "input"))
    )
    (net (code "146") (name "Net-(U143-DOUT)") (class "Default")
      (node (ref "U143") (pin "2") (pinfunction "DOUT_2") (pintype "output"))
      (node (ref "U144") (pin "4") (pinfunction "DIN_4") (pintype "input"))
    )
    (net (code "147") (name "Net-(U144-DOUT)") (class "Default")
      (node (ref "U144") (pin "2") (pinfunction "DOUT_2") (pintype "output"))
      (node (ref "U145") (pin "4") (pinfunction "DIN_4") (pintype "input"))
    )
    (net (code "148") (name "Net-(U145-DOUT)") (class "Default")
      (node (ref "U145") (pin "2") (pinfunction "DOUT_2") (pintype "output"))
      (node (ref "U146") (pin "4") (pinfunction "DIN_4") (pintype "input"))
    )
    (net (code "149") (name "Net-(U146-DOUT)") (class "Default")
      (node (ref "U146") (pin "2") (pinfunction "DOUT_2") (pintype "output"))
      (node (ref "U147") (pin "4") (pinfunction "DIN_4") (pintype "input"))
    )
    (net (code "150") (name "Net-(U147-DOUT)") (class "Default")
      (node (ref "U147") (pin "2") (pinfunction "DOUT_2") (pintype "output"))
      (node (ref "U148") (pin "4") (pinfunction "DIN_4") (pintype "input"))
    )
    (net (code "151") (name "Net-(U148-DOUT)") (class "Default")
      (node (ref "U148") (pin "2") (pinfunction "DOUT_2") (pintype "output"))
      (node (ref "U149") (pin "4") (pinfunction "DIN_4") (pintype "input"))
    )
    (net (code "152") (name "Net-(U149-DOUT)") (class "Default")
      (node (ref "U149") (pin "2") (pinfunction "DOUT_2") (pintype "output"))
      (node (ref "U150") (pin "4") (pinfunction "DIN_4") (pintype "input"))
    )
    (net (code "153") (name "Net-(U150-DOUT)") (class "Default")
      (node (ref "U150") (pin "2") (pinfunction "DOUT_2") (pintype "output"))
      (node (ref "U151") (pin "4") (pinfunction "DIN_4") (pintype "input"))
    )
    (net (code "154") (name "Net-(U151-DOUT)") (class "Default")
      (node (ref "U151") (pin "2") (pinfunction "DOUT_2") (pintype "output"))
      (node (ref "U152") (pin "4") (pinfunction "DIN_4") (pintype "input"))
    )
    (net (code "155") (name "Net-(U152-DOUT)") (class "Default")
      (node (ref "U152") (pin "2") (pinfunction "DOUT_2") (pintype "output"))
      (node (ref "U153") (pin "4") (pinfunction "DIN_4") (pintype "input"))
    )
    (net (code "156") (name "Net-(U153-DOUT)") (class "Default")
      (node (ref "U153") (pin "2") (pinfunction "DOUT_2") (pintype "output"))
      (node (ref "U154") (pin "4") (pinfunction "DIN_4") (pintype "input"))
    )
    (net (code "157") (name "Net-(U154-DOUT)") (class "Default")
      (node (ref "U154") (pin "2") (pinfunction "DOUT_2") (pintype "output"))
      (node (ref "U155") (pin "4") (pinfunction "DIN_4") (pintype "input"))
    )
    (net (code "158") (name "Net-(U155-DOUT)") (class "Default")
      (node (ref "U155") (pin "2") (pinfunction "DOUT_2") (pintype "output"))
      (node (ref "U156") (pin "4") (pinfunction "DIN_4") (pintype "input"))
    )
    (net (code "159") (name "Net-(U156-DOUT)") (class "Default")
      (node (ref "U156") (pin "2") (pinfunction "DOUT_2") (pintype "output"))
      (node (ref "U157") (pin "4") (pinfunction "DIN_4") (pintype "input"))
    )
    (net (code "160") (name "Net-(U157-DOUT)") (class "Default")
      (node (ref "U157") (pin "2") (pinfunction "DOUT_2") (pintype "output"))
      (node (ref "U158") (pin "4") (pinfunction "DIN_4") (pintype "input"))
    )
    (net (code "161") (name "Net-(U158-DOUT)") (class "Default")
      (node (ref "U158") (pin "2") (pinfunction "DOUT_2") (pintype "output"))
      (node (ref "U159") (pin "4") (pinfunction "DIN_4") (pintype "input"))
    )
    (net (code "162") (name "Net-(U159-DOUT)") (class "Default")
      (node (ref "U159") (pin "2") (pinfunction "DOUT_2") (pintype "output"))
      (node (ref "U160") (pin "4") (pinfunction "DIN_4") (pintype "input"))
    )
    (net (code "163") (name "Net-(U161-DOUT)") (class "Default")
      (node (ref "U161") (pin "2") (pinfunction "DOUT_2") (pintype "output"))
      (node (ref "U162") (pin "4") (pinfunction "DIN_4") (pintype "input"))
    )
    (net (code "164") (name "Net-(U162-DOUT)") (class "Default")
      (node (ref "U162") (pin "2") (pinfunction "DOUT_2") (pintype "output"))
      (node (ref "U163") (pin "4") (pinfunction "DIN_4") (pintype "input"))
    )
    (net (code "165") (name "Net-(U163-DOUT)") (class "Default")
      (node (ref "U163") (pin "2") (pinfunction "DOUT_2") (pintype "output"))
      (node (ref "U164") (pin "4") (pinfunction "DIN_4") (pintype "input"))
    )
    (net (code "166") (name "Net-(U164-DOUT)") (class "Default")
      (node (ref "U164") (pin "2") (pinfunction "DOUT_2") (pintype "output"))
      (node (ref "U165") (pin "4") (pinfunction "DIN_4") (pintype "input"))
    )
    (net (code "167") (name "Net-(U165-DOUT)") (class "Default")
      (node (ref "U165") (pin "2") (pinfunction "DOUT_2") (pintype "output"))
      (node (ref "U166") (pin "4") (pinfunction "DIN_4") (pintype "input"))
    )
    (net (code "168") (name "Net-(U166-DOUT)") (class "Default")
      (node (ref "U166") (pin "2") (pinfunction "DOUT_2") (pintype "output"))
      (node (ref "U167") (pin "4") (pinfunction "DIN_4") (pintype "input"))
    )
    (net (code "169") (name "Net-(U167-DOUT)") (class "Default")
      (node (ref "U167") (pin "2") (pinfunction "DOUT_2") (pintype "output"))
      (node (ref "U168") (pin "4") (pinfunction "DIN_4") (pintype "input"))
    )
    (net (code "170") (name "Net-(U168-DOUT)") (class "Default")
      (node (ref "U168") (pin "2") (pinfunction "DOUT_2") (pintype "output"))
      (node (ref "U169") (pin "4") (pinfunction "DIN_4") (pintype "input"))
    )
    (net (code "171") (name "Net-(U169-DOUT)") (class "Default")
      (node (ref "U169") (pin "2") (pinfunction "DOUT_2") (pintype "output"))
      (node (ref "U170") (pin "4") (pinfunction "DIN_4") (pintype "input"))
    )
    (net (code "172") (name "Net-(U170-DOUT)") (class "Default")
      (node (ref "U170") (pin "2") (pinfunction "DOUT_2") (pintype "output"))
      (node (ref "U171") (pin "4") (pinfunction "DIN_4") (pintype "input"))
    )
    (net (code "173") (name "Net-(U171-DOUT)") (class "Default")
      (node (ref "U171") (pin "2") (pinfunction "DOUT_2") (pintype "output"))
      (node (ref "U172") (pin "4") (pinfunction "DIN_4") (pintype "input"))
    )
    (net (code "174") (name "Net-(U172-DOUT)") (class "Default")
      (node (ref "U172") (pin "2") (pinfunction "DOUT_2") (pintype "output"))
      (node (ref "U173") (pin "4") (pinfunction "DIN_4") (pintype "input"))
    )
    (net (code "175") (name "Net-(U173-DOUT)") (class "Default")
      (node (ref "U173") (pin "2") (pinfunction "DOUT_2") (pintype "output"))
      (node (ref "U174") (pin "4") (pinfunction "DIN_4") (pintype "input"))
    )
    (net (code "176") (name "Net-(U174-DOUT)") (class "Default")
      (node (ref "U174") (pin "2") (pinfunction "DOUT_2") (pintype "output"))
      (node (ref "U175") (pin "4") (pinfunction "DIN_4") (pintype "input"))
    )
    (net (code "177") (name "Net-(U175-DOUT)") (class "Default")
      (node (ref "U175") (pin "2") (pinfunction "DOUT_2") (pintype "output"))
      (node (ref "U176") (pin "4") (pinfunction "DIN_4") (pintype "input"))
    )
    (net (code "178") (name "Net-(U176-DOUT)") (class "Default")
      (node (ref "U176") (pin "2") (pinfunction "DOUT_2") (pintype "output"))
      (node (ref "U177") (pin "4") (pinfunction "DIN_4") (pintype "input"))
    )
    (net (code "179") (name "Net-(U177-DOUT)") (class "Default")
      (node (ref "U177") (pin "2") (pinfunction "DOUT_2") (pintype "output"))
      (node (ref "U178") (pin "4") (pinfunction "DIN_4") (pintype "input"))
    )
    (net (code "180") (name "Net-(U178-DOUT)") (class "Default")
      (node (ref "U178") (pin "2") (pinfunction "DOUT_2") (pintype "output"))
      (node (ref "U179") (pin "4") (pinfunction "DIN_4") (pintype "input"))
    )
    (net (code "181") (name "Net-(U179-DOUT)") (class "Default")
      (node (ref "U179") (pin "2") (pinfunction "DOUT_2") (pintype "output"))
      (node (ref "U180") (pin "4") (pinfunction "DIN_4") (pintype "input"))
    )
    (net (code "182") (name "Net-(U180-DOUT)") (class "Default")
      (node (ref "U180") (pin "2") (pinfunction "DOUT_2") (pintype "output"))
      (node (ref "U181") (pin "4") (pinfunction "DIN_4") (pintype "input"))
    )
    (net (code "183") (name "Net-(U181-DOUT)") (class "Default")
      (node (ref "U181") (pin "2") (pinfunction "DOUT_2") (pintype "output"))
      (node (ref "U182") (pin "4") (pinfunction "DIN_4") (pintype "input"))
    )
    (net (code "184") (name "Net-(U182-DOUT)") (class "Default")
      (node (ref "U182") (pin "2") (pinfunction "DOUT_2") (pintype "output"))
      (node (ref "U183") (pin "4") (pinfunction "DIN_4") (pintype "input"))
    )
    (net (code "185") (name "Net-(U183-DOUT)") (class "Default")
      (node (ref "U183") (pin "2") (pinfunction "DOUT_2") (pintype "output"))
      (node (ref "U184") (pin "4") (pinfunction "DIN_4") (pintype "input"))
    )
    (net (code "186") (name "Net-(U184-DOUT)") (class "Default")
      (node (ref "U184") (pin "2") (pinfunction "DOUT_2") (pintype "output"))
      (node (ref "U185") (pin "4") (pinfunction "DIN_4") (pintype "input"))
    )
    (net (code "187") (name "Net-(U185-DOUT)") (class "Default")
      (node (ref "U185") (pin "2") (pinfunction "DOUT_2") (pintype "output"))
      (node (ref "U186") (pin "4") (pinfunction "DIN_4") (pintype "input"))
    )
    (net (code "188") (name "Net-(U186-DOUT)") (class "Default")
      (node (ref "U186") (pin "2") (pinfunction "DOUT_2") (pintype "output"))
      (node (ref "U187") (pin "4") (pinfunction "DIN_4") (pintype "input"))
    )
    (net (code "189") (name "Net-(U187-DOUT)") (class "Default")
      (node (ref "U187") (pin "2") (pinfunction "DOUT_2") (pintype "output"))
      (node (ref "U188") (pin "4") (pinfunction "DIN_4") (pintype "input"))
    )
    (net (code "190") (name "Net-(U188-DOUT)") (class "Default")
      (node (ref "U188") (pin "2") (pinfunction "DOUT_2") (pintype "output"))
      (node (ref "U189") (pin "4") (pinfunction "DIN_4") (pintype "input"))
    )
    (net (code "191") (name "Net-(U189-DOUT)") (class "Default")
      (node (ref "U189") (pin "2") (pinfunction "DOUT_2") (pintype "output"))
      (node (ref "U190") (pin "4") (pinfunction "DIN_4") (pintype "input"))
    )
    (net (code "192") (name "Net-(U190-DOUT)") (class "Default")
      (node (ref "U190") (pin "2") (pinfunction "DOUT_2") (pintype "output"))
      (node (ref "U191") (pin "4") (pinfunction "DIN_4") (pintype "input"))
    )
    (net (code "193") (name "Net-(U191-DOUT)") (class "Default")
      (node (ref "U191") (pin "2") (pinfunction "DOUT_2") (pintype "output"))
      (node (ref "U192") (pin "4") (pinfunction "DIN_4") (pintype "input"))
    )
    (net (code "194") (name "Net-(U192-DOUT)") (class "Default")
      (node (ref "U192") (pin "2") (pinfunction "DOUT_2") (pintype "output"))
      (node (ref "U193") (pin "4") (pinfunction "DIN_4") (pintype "input"))
    )
    (net (code "195") (name "Net-(U193-DOUT)") (class "Default")
      (node (ref "U193") (pin "2") (pinfunction "DOUT_2") (pintype "output"))
      (node (ref "U194") (pin "4") (pinfunction "DIN_4") (pintype "input"))
    )
    (net (code "196") (name "Net-(U194-DOUT)") (class "Default")
      (node (ref "U194") (pin "2") (pinfunction "DOUT_2") (pintype "output"))
      (node (ref "U195") (pin "4") (pinfunction "DIN_4") (pintype "input"))
    )
    (net (code "197") (name "Net-(U195-DOUT)") (class "Default")
      (node (ref "U195") (pin "2") (pinfunction "DOUT_2") (pintype "output"))
      (node (ref "U196") (pin "4") (pinfunction "DIN_4") (pintype "input"))
    )
    (net (code "198") (name "Net-(U196-DOUT)") (class "Default")
      (node (ref "U196") (pin "2") (pinfunction "DOUT_2") (pintype "output"))
      (node (ref "U197") (pin "4") (pinfunction "DIN_4") (pintype "input"))
    )
    (net (code "199") (name "Net-(U197-DOUT)") (class "Default")
      (node (ref "U197") (pin "2") (pinfunction "DOUT_2") (pintype "output"))
      (node (ref "U198") (pin "4") (pinfunction "DIN_4") (pintype "input"))
    )
    (net (code "200") (name "Net-(U198-DOUT)") (class "Default")
      (node (ref "U198") (pin "2") (pinfunction "DOUT_2") (pintype "output"))
      (node (ref "U199") (pin "4") (pinfunction "DIN_4") (pintype "input"))
    )
    (net (code "201") (name "Net-(U199-DOUT)") (class "Default")
      (node (ref "U199") (pin "2") (pinfunction "DOUT_2") (pintype "output"))
      (node (ref "U200") (pin "4") (pinfunction "DIN_4") (pintype "input"))
    )
    (net (code "202") (name "Net-(U200-DOUT)") (class "Default")
      (node (ref "U200") (pin "2") (pinfunction "DOUT_2") (pintype "output"))
      (node (ref "U201") (pin "4") (pinfunction "DIN_4") (pintype "input"))
    )
    (net (code "203") (name "Net-(U201-DOUT)") (class "Default")
      (node (ref "U201") (pin "2") (pinfunction "DOUT_2") (pintype "output"))
      (node (ref "U202") (pin "4") (pinfunction "DIN_4") (pintype "input"))
    )
    (net (code "204") (name "Net-(U202-DOUT)") (class "Default")
      (node (ref "U202") (pin "2") (pinfunction "DOUT_2") (pintype "output"))
      (node (ref "U203") (pin "4") (pinfunction "DIN_4") (pintype "input"))
    )
    (net (code "205") (name "Net-(U203-DOUT)") (class "Default")
      (node (ref "U203") (pin "2") (pinfunction "DOUT_2") (pintype "output"))
      (node (ref "U204") (pin "4") (pinfunction "DIN_4") (pintype "input"))
    )
    (net (code "206") (name "Net-(U204-DOUT)") (class "Default")
      (node (ref "U204") (pin "2") (pinfunction "DOUT_2") (pintype "output"))
      (node (ref "U205") (pin "4") (pinfunction "DIN_4") (pintype "input"))
    )
    (net (code "207") (name "Net-(U205-DOUT)") (class "Default")
      (node (ref "U205") (pin "2") (pinfunction "DOUT_2") (pintype "output"))
      (node (ref "U206") (pin "4") (pinfunction "DIN_4") (pintype "input"))
    )
    (net (code "208") (name "Net-(U206-DOUT)") (class "Default")
      (node (ref "U206") (pin "2") (pinfunction "DOUT_2") (pintype "output"))
      (node (ref "U207") (pin "4") (pinfunction "DIN_4") (pintype "input"))
    )
    (net (code "209") (name "Net-(U207-DOUT)") (class "Default")
      (node (ref "U207") (pin "2") (pinfunction "DOUT_2") (pintype "output"))
      (node (ref "U208") (pin "4") (pinfunction "DIN_4") (pintype "input"))
    )
    (net (code "210") (name "Net-(U208-DOUT)") (class "Default")
      (node (ref "U208") (pin "2") (pinfunction "DOUT_2") (pintype "output"))
      (node (ref "U209") (pin "4") (pinfunction "DIN_4") (pintype "input"))
    )
    (net (code "211") (name "Net-(U209-DOUT)") (class "Default")
      (node (ref "U209") (pin "2") (pinfunction "DOUT_2") (pintype "output"))
      (node (ref "U210") (pin "4") (pinfunction "DIN_4") (pintype "input"))
    )
    (net (code "212") (name "Net-(U210-DOUT)") (class "Default")
      (node (ref "U210") (pin "2") (pinfunction "DOUT_2") (pintype "output"))
      (node (ref "U211") (pin "4") (pinfunction "DIN_4") (pintype "input"))
    )
    (net (code "213") (name "Net-(U211-DOUT)") (class "Default")
      (node (ref "U211") (pin "2") (pinfunction "DOUT_2") (pintype "output"))
      (node (ref "U212") (pin "4") (pinfunction "DIN_4") (pintype "input"))
    )
    (net (code "214") (name "Net-(U212-DOUT)") (class "Default")
      (node (ref "U212") (pin "2") (pinfunction "DOUT_2") (pintype "output"))
      (node (ref "U213") (pin "4") (pinfunction "DIN_4") (pintype "input"))
    )
    (net (code "215") (name "Net-(U213-DOUT)") (class "Default")
      (node (ref "U213") (pin "2") (pinfunction "DOUT_2") (pintype "output"))
      (node (ref "U214") (pin "4") (pinfunction "DIN_4") (pintype "input"))
    )
    (net (code "216") (name "Net-(U214-DOUT)") (class "Default")
      (node (ref "U214") (pin "2") (pinfunction "DOUT_2") (pintype "output"))
      (node (ref "U215") (pin "4") (pinfunction "DIN_4") (pintype "input"))
    )
    (net (code "217") (name "Net-(U215-DOUT)") (class "Default")
      (node (ref "U215") (pin "2") (pinfunction "DOUT_2") (pintype "output"))
      (node (ref "U216") (pin "4") (pinfunction "DIN_4") (pintype "input"))
    )
    (net (code "218") (name "Net-(U216-DOUT)") (class "Default")
      (node (ref "U216") (pin "2") (pinfunction "DOUT_2") (pintype "output"))
      (node (ref "U217") (pin "4") (pinfunction "DIN_4") (pintype "input"))
    )
    (net (code "219") (name "Net-(U217-DOUT)") (class "Default")
      (node (ref "U217") (pin "2") (pinfunction "DOUT_2") (pintype "output"))
      (node (ref "U218") (pin "4") (pinfunction "DIN_4") (pintype "input"))
    )
    (net (code "220") (name "Net-(U218-DOUT)") (class "Default")
      (node (ref "U218") (pin "2") (pinfunction "DOUT_2") (pintype "output"))
      (node (ref "U219") (pin "4") (pinfunction "DIN_4") (pintype "input"))
    )
    (net (code "221") (name "Net-(U219-DOUT)") (class "Default")
      (node (ref "U219") (pin "2") (pinfunction "DOUT_2") (pintype "output"))
      (node (ref "U220") (pin "4") (pinfunction "DIN_4") (pintype "input"))
    )
    (net (code "222") (name "VCC") (class "Default")
      (node (ref "U1") (pin "1") (pinfunction "VDD_1") (pintype "power_in"))
      (node (ref "U10") (pin "1") (pinfunction "VDD_1") (pintype "power_in"))
      (node (ref "U100") (pin "1") (pinfunction "VDD_1") (pintype "power_in"))
      (node (ref "U101") (pin "1") (pinfunction "VDD_1") (pintype "power_in"))
      (node (ref "U102") (pin "1") (pinfunction "VDD_1") (pintype "power_in"))
      (node (ref "U103") (pin "1") (pinfunction "VDD_1") (pintype "power_in"))
      (node (ref "U104") (pin "1") (pinfunction "VDD_1") (pintype "power_in"))
      (node (ref "U105") (pin "1") (pinfunction "VDD_1") (pintype "power_in"))
      (node (ref "U106") (pin "1") (pinfunction "VDD_1") (pintype "power_in"))
      (node (ref "U107") (pin "1") (pinfunction "VDD_1") (pintype "power_in"))
      (node (ref "U108") (pin "1") (pinfunction "VDD_1") (pintype "power_in"))
      (node (ref "U109") (pin "1") (pinfunction "VDD_1") (pintype "power_in"))
      (node (ref "U11") (pin "1") (pinfunction "VDD_1") (pintype "power_in"))
      (node (ref "U110") (pin "1") (pinfunction "VDD_1") (pintype "power_in"))
      (node (ref "U111") (pin "1") (pinfunction "VDD_1") (pintype "power_in"))
      (node (ref "U112") (pin "1") (pinfunction "VDD_1") (pintype "power_in"))
      (node (ref "U113") (pin "1") (pinfunction "VDD_1") (pintype "power_in"))
      (node (ref "U114") (pin "1") (pinfunction "VDD_1") (pintype "power_in"))
      (node (ref "U115") (pin "1") (pinfunction "VDD_1") (pintype "power_in"))
      (node (ref "U116") (pin "1") (pinfunction "VDD_1") (pintype "power_in"))
      (node (ref "U117") (pin "1") (pinfunction "VDD_1") (pintype "power_in"))
      (node (ref "U118") (pin "1") (pinfunction "VDD_1") (pintype "power_in"))
      (node (ref "U119") (pin "1") (pinfunction "VDD_1") (pintype "power_in"))
      (node (ref "U12") (pin "1") (pinfunction "VDD_1") (pintype "power_in"))
      (node (ref "U120") (pin "1") (pinfunction "VDD_1") (pintype "power_in"))
      (node (ref "U121") (pin "1") (pinfunction "VDD_1") (pintype "power_in"))
      (node (ref "U122") (pin "1") (pinfunction "VDD_1") (pintype "power_in"))
      (node (ref "U123") (pin "1") (pinfunction "VDD_1") (pintype "power_in"))
      (node (ref "U124") (pin "1") (pinfunction "VDD_1") (pintype "power_in"))
      (node (ref "U125") (pin "1") (pinfunction "VDD_1") (pintype "power_in"))
      (node (ref "U126") (pin "1") (pinfunction "VDD_1") (pintype "power_in"))
      (node (ref "U127") (pin "1") (pinfunction "VDD_1") (pintype "power_in"))
      (node (ref "U128") (pin "1") (pinfunction "VDD_1") (pintype "power_in"))
      (node (ref "U129") (pin "1") (pinfunction "VDD_1") (pintype "power_in"))
      (node (ref "U13") (pin "1") (pinfunction "VDD_1") (pintype "power_in"))
      (node (ref "U130") (pin "1") (pinfunction "VDD_1") (pintype "power_in"))
      (node (ref "U131") (pin "1") (pinfunction "VDD_1") (pintype "power_in"))
      (node (ref "U132") (pin "1") (pinfunction "VDD_1") (pintype "power_in"))
      (node (ref "U133") (pin "1") (pinfunction "VDD_1") (pintype "power_in"))
      (node (ref "U134") (pin "1") (pinfunction "VDD_1") (pintype "power_in"))
      (node (ref "U135") (pin "1") (pinfunction "VDD_1") (pintype "power_in"))
      (node (ref "U136") (pin "1") (pinfunction "VDD_1") (pintype "power_in"))
      (node (ref "U137") (pin "1") (pinfunction "VDD_1") (pintype "power_in"))
      (node (ref "U138") (pin "1") (pinfunction "VDD_1") (pintype "power_in"))
      (node (ref "U139") (pin "1") (pinfunction "VDD_1") (pintype "power_in"))
      (node (ref "U14") (pin "1") (pinfunction "VDD_1") (pintype "power_in"))
      (node (ref "U140") (pin "1") (pinfunction "VDD_1") (pintype "power_in"))
      (node (ref "U141") (pin "1") (pinfunction "VDD_1") (pintype "power_in"))
      (node (ref "U142") (pin "1") (pinfunction "VDD_1") (pintype "power_in"))
      (node (ref "U143") (pin "1") (pinfunction "VDD_1") (pintype "power_in"))
      (node (ref "U144") (pin "1") (pinfunction "VDD_1") (pintype "power_in"))
      (node (ref "U145") (pin "1") (pinfunction "VDD_1") (pintype "power_in"))
      (node (ref "U146") (pin "1") (pinfunction "VDD_1") (pintype "power_in"))
      (node (ref "U147") (pin "1") (pinfunction "VDD_1") (pintype "power_in"))
      (node (ref "U148") (pin "1") (pinfunction "VDD_1") (pintype "power_in"))
      (node (ref "U149") (pin "1") (pinfunction "VDD_1") (pintype "power_in"))
      (node (ref "U15") (pin "1") (pinfunction "VDD_1") (pintype "power_in"))
      (node (ref "U150") (pin "1") (pinfunction "VDD_1") (pintype "power_in"))
      (node (ref "U151") (pin "1") (pinfunction "VDD_1") (pintype "power_in"))
      (node (ref "U152") (pin "1") (pinfunction "VDD_1") (pintype "power_in"))
      (node (ref "U153") (pin "1") (pinfunction "VDD_1") (pintype "power_in"))
      (node (ref "U154") (pin "1") (pinfunction "VDD_1") (pintype "power_in"))
      (node (ref "U155") (pin "1") (pinfunction "VDD_1") (pintype "power_in"))
      (node (ref "U156") (pin "1") (pinfunction "VDD_1") (pintype "power_in"))
      (node (ref "U157") (pin "1") (pinfunction "VDD_1") (pintype "power_in"))
      (node (ref "U158") (pin "1") (pinfunction "VDD_1") (pintype "power_in"))
      (node (ref "U159") (pin "1") (pinfunction "VDD_1") (pintype "power_in"))
      (node (ref "U16") (pin "1") (pinfunction "VDD_1") (pintype "power_in"))
      (node (ref "U160") (pin "1") (pinfunction "VDD_1") (pintype "power_in"))
      (node (ref "U161") (pin "1") (pinfunction "VDD_1") (pintype "power_in"))
      (node (ref "U162") (pin "1") (pinfunction "VDD_1") (pintype "power_in"))
      (node (ref "U163") (pin "1") (pinfunction "VDD_1") (pintype "power_in"))
      (node (ref "U164") (pin "1") (pinfunction "VDD_1") (pintype "power_in"))
      (node (ref "U165") (pin "1") (pinfunction "VDD_1") (pintype "power_in"))
      (node (ref "U166") (pin "1") (pinfunction "VDD_1") (pintype "power_in"))
      (node (ref "U167") (pin "1") (pinfunction "VDD_1") (pintype "power_in"))
      (node (ref "U168") (pin "1") (pinfunction "VDD_1") (pintype "power_in"))
      (node (ref "U169") (pin "1") (pinfunction "VDD_1") (pintype "power_in"))
      (node (ref "U17") (pin "1") (pinfunction "VDD_1") (pintype "power_in"))
      (node (ref "U170") (pin "1") (pinfunction "VDD_1") (pintype "power_in"))
      (node (ref "U171") (pin "1") (pinfunction "VDD_1") (pintype "power_in"))
      (node (ref "U172") (pin "1") (pinfunction "VDD_1") (pintype "power_in"))
      (node (ref "U173") (pin "1") (pinfunction "VDD_1") (pintype "power_in"))
      (node (ref "U174") (pin "1") (pinfunction "VDD_1") (pintype "power_in"))
      (node (ref "U175") (pin "1") (pinfunction "VDD_1") (pintype "power_in"))
      (node (ref "U176") (pin "1") (pinfunction "VDD_1") (pintype "power_in"))
      (node (ref "U177") (pin "1") (pinfunction "VDD_1") (pintype "power_in"))
      (node (ref "U178") (pin "1") (pinfunction "VDD_1") (pintype "power_in"))
      (node (ref "U179") (pin "1") (pinfunction "VDD_1") (pintype "power_in"))
      (node (ref "U18") (pin "1") (pinfunction "VDD_1") (pintype "power_in"))
      (node (ref "U180") (pin "1") (pinfunction "VDD_1") (pintype "power_in"))
      (node (ref "U181") (pin "1") (pinfunction "VDD_1") (pintype "power_in"))
      (node (ref "U182") (pin "1") (pinfunction "VDD_1") (pintype "power_in"))
      (node (ref "U183") (pin "1") (pinfunction "VDD_1") (pintype "power_in"))
      (node (ref "U184") (pin "1") (pinfunction "VDD_1") (pintype "power_in"))
      (node (ref "U185") (pin "1") (pinfunction "VDD_1") (pintype "power_in"))
      (node (ref "U186") (pin "1") (pinfunction "VDD_1") (pintype "power_in"))
      (node (ref "U187") (pin "1") (pinfunction "VDD_1") (pintype "power_in"))
      (node (ref "U188") (pin "1") (pinfunction "VDD_1") (pintype "power_in"))
      (node (ref "U189") (pin "1") (pinfunction "VDD_1") (pintype "power_in"))
      (node (ref "U19") (pin "1") (pinfunction "VDD_1") (pintype "power_in"))
      (node (ref "U190") (pin "1") (pinfunction "VDD_1") (pintype "power_in"))
      (node (ref "U191") (pin "1") (pinfunction "VDD_1") (pintype "power_in"))
      (node (ref "U192") (pin "1") (pinfunction "VDD_1") (pintype "power_in"))
      (node (ref "U193") (pin "1") (pinfunction "VDD_1") (pintype "power_in"))
      (node (ref "U194") (pin "1") (pinfunction "VDD_1") (pintype "power_in"))
      (node (ref "U195") (pin "1") (pinfunction "VDD_1") (pintype "power_in"))
      (node (ref "U196") (pin "1") (pinfunction "VDD_1") (pintype "power_in"))
      (node (ref "U197") (pin "1") (pinfunction "VDD_1") (pintype "power_in"))
      (node (ref "U198") (pin "1") (pinfunction "VDD_1") (pintype "power_in"))
      (node (ref "U199") (pin "1") (pinfunction "VDD_1") (pintype "power_in"))
      (node (ref "U2") (pin "1") (pinfunction "VDD_1") (pintype "power_in"))
      (node (ref "U20") (pin "1") (pinfunction "VDD_1") (pintype "power_in"))
      (node (ref "U200") (pin "1") (pinfunction "VDD_1") (pintype "power_in"))
      (node (ref "U201") (pin "1") (pinfunction "VDD_1") (pintype "power_in"))
      (node (ref "U202") (pin "1") (pinfunction "VDD_1") (pintype "power_in"))
      (node (ref "U203") (pin "1") (pinfunction "VDD_1") (pintype "power_in"))
      (node (ref "U204") (pin "1") (pinfunction "VDD_1") (pintype "power_in"))
      (node (ref "U205") (pin "1") (pinfunction "VDD_1") (pintype "power_in"))
      (node (ref "U206") (pin "1") (pinfunction "VDD_1") (pintype "power_in"))
      (node (ref "U207") (pin "1") (pinfunction "VDD_1") (pintype "power_in"))
      (node (ref "U208") (pin "1") (pinfunction "VDD_1") (pintype "power_in"))
      (node (ref "U209") (pin "1") (pinfunction "VDD_1") (pintype "power_in"))
      (node (ref "U21") (pin "1") (pinfunction "VDD_1") (pintype "power_in"))
      (node (ref "U210") (pin "1") (pinfunction "VDD_1") (pintype "power_in"))
      (node (ref "U211") (pin "1") (pinfunction "VDD_1") (pintype "power_in"))
      (node (ref "U212") (pin "1") (pinfunction "VDD_1") (pintype "power_in"))
      (node (ref "U213") (pin "1") (pinfunction "VDD_1") (pintype "power_in"))
      (node (ref "U214") (pin "1") (pinfunction "VDD_1") (pintype "power_in"))
      (node (ref "U215") (pin "1") (pinfunction "VDD_1") (pintype "power_in"))
      (node (ref "U216") (pin "1") (pinfunction "VDD_1") (pintype "power_in"))
      (node (ref "U217") (pin "1") (pinfunction "VDD_1") (pintype "power_in"))
      (node (ref "U218") (pin "1") (pinfunction "VDD_1") (pintype "power_in"))
      (node (ref "U219") (pin "1") (pinfunction "VDD_1") (pintype "power_in"))
      (node (ref "U22") (pin "1") (pinfunction "VDD_1") (pintype "power_in"))
      (node (ref "U220") (pin "1") (pinfunction "VDD_1") (pintype "power_in"))
      (node (ref "U23") (pin "1") (pinfunction "VDD_1") (pintype "power_in"))
      (node (ref "U24") (pin "1") (pinfunction "VDD_1") (pintype "power_in"))
      (node (ref "U25") (pin "1") (pinfunction "VDD_1") (pintype "power_in"))
      (node (ref "U26") (pin "1") (pinfunction "VDD_1") (pintype "power_in"))
      (node (ref "U27") (pin "1") (pinfunction "VDD_1") (pintype "power_in"))
      (node (ref "U28") (pin "1") (pinfunction "VDD_1") (pintype "power_in"))
      (node (ref "U29") (pin "1") (pinfunction "VDD_1") (pintype "power_in"))
      (node (ref "U3") (pin "1") (pinfunction "VDD_1") (pintype "power_in"))
      (node (ref "U30") (pin "1") (pinfunction "VDD_1") (pintype "power_in"))
      (node (ref "U31") (pin "1") (pinfunction "VDD_1") (pintype "power_in"))
      (node (ref "U32") (pin "1") (pinfunction "VDD_1") (pintype "power_in"))
      (node (ref "U33") (pin "1") (pinfunction "VDD_1") (pintype "power_in"))
      (node (ref "U34") (pin "1") (pinfunction "VDD_1") (pintype "power_in"))
      (node (ref "U35") (pin "1") (pinfunction "VDD_1") (pintype "power_in"))
      (node (ref "U36") (pin "1") (pinfunction "VDD_1") (pintype "power_in"))
      (node (ref "U37") (pin "1") (pinfunction "VDD_1") (pintype "power_in"))
      (node (ref "U38") (pin "1") (pinfunction "VDD_1") (pintype "power_in"))
      (node (ref "U39") (pin "1") (pinfunction "VDD_1") (pintype "power_in"))
      (node (ref "U4") (pin "1") (pinfunction "VDD_1") (pintype "power_in"))
      (node (ref "U40") (pin "1") (pinfunction "VDD_1") (pintype "power_in"))
      (node (ref "U41") (pin "1") (pinfunction "VDD_1") (pintype "power_in"))
      (node (ref "U42") (pin "1") (pinfunction "VDD_1") (pintype "power_in"))
      (node (ref "U43") (pin "1") (pinfunction "VDD_1") (pintype "power_in"))
      (node (ref "U44") (pin "1") (pinfunction "VDD_1") (pintype "power_in"))
      (node (ref "U45") (pin "1") (pinfunction "VDD_1") (pintype "power_in"))
      (node (ref "U46") (pin "1") (pinfunction "VDD_1") (pintype "power_in"))
      (node (ref "U47") (pin "1") (pinfunction "VDD_1") (pintype "power_in"))
      (node (ref "U48") (pin "1") (pinfunction "VDD_1") (pintype "power_in"))
      (node (ref "U49") (pin "1") (pinfunction "VDD_1") (pintype "power_in"))
      (node (ref "U5") (pin "1") (pinfunction "VDD_1") (pintype "power_in"))
      (node (ref "U50") (pin "1") (pinfunction "VDD_1") (pintype "power_in"))
      (node (ref "U51") (pin "1") (pinfunction "VDD_1") (pintype "power_in"))
      (node (ref "U52") (pin "1") (pinfunction "VDD_1") (pintype "power_in"))
      (node (ref "U53") (pin "1") (pinfunction "VDD_1") (pintype "power_in"))
      (node (ref "U54") (pin "1") (pinfunction "VDD_1") (pintype "power_in"))
      (node (ref "U55") (pin "1") (pinfunction "VDD_1") (pintype "power_in"))
      (node (ref "U56") (pin "1") (pinfunction "VDD_1") (pintype "power_in"))
      (node (ref "U57") (pin "1") (pinfunction "VDD_1") (pintype "power_in"))
      (node (ref "U58") (pin "1") (pinfunction "VDD_1") (pintype "power_in"))
      (node (ref "U59") (pin "1") (pinfunction "VDD_1") (pintype "power_in"))
      (node (ref "U6") (pin "1") (pinfunction "VDD_1") (pintype "power_in"))
      (node (ref "U60") (pin "1") (pinfunction "VDD_1") (pintype "power_in"))
      (node (ref "U61") (pin "1") (pinfunction "VDD_1") (pintype "power_in"))
      (node (ref "U62") (pin "1") (pinfunction "VDD_1") (pintype "power_in"))
      (node (ref "U63") (pin "1") (pinfunction "VDD_1") (pintype "power_in"))
      (node (ref "U64") (pin "1") (pinfunction "VDD_1") (pintype "power_in"))
      (node (ref "U65") (pin "1") (pinfunction "VDD_1") (pintype "power_in"))
      (node (ref "U66") (pin "1") (pinfunction "VDD_1") (pintype "power_in"))
      (node (ref "U67") (pin "1") (pinfunction "VDD_1") (pintype "power_in"))
      (node (ref "U68") (pin "1") (pinfunction "VDD_1") (pintype "power_in"))
      (node (ref "U69") (pin "1") (pinfunction "VDD_1") (pintype "power_in"))
      (node (ref "U7") (pin "1") (pinfunction "VDD_1") (pintype "power_in"))
      (node (ref "U70") (pin "1") (pinfunction "VDD_1") (pintype "power_in"))
      (node (ref "U71") (pin "1") (pinfunction "VDD_1") (pintype "power_in"))
      (node (ref "U72") (pin "1") (pinfunction "VDD_1") (pintype "power_in"))
      (node (ref "U73") (pin "1") (pinfunction "VDD_1") (pintype "power_in"))
      (node (ref "U74") (pin "1") (pinfunction "VDD_1") (pintype "power_in"))
      (node (ref "U75") (pin "1") (pinfunction "VDD_1") (pintype "power_in"))
      (node (ref "U76") (pin "1") (pinfunction "VDD_1") (pintype "power_in"))
      (node (ref "U77") (pin "1") (pinfunction "VDD_1") (pintype "power_in"))
      (node (ref "U78") (pin "1") (pinfunction "VDD_1") (pintype "power_in"))
      (node (ref "U79") (pin "1") (pinfunction "VDD_1") (pintype "power_in"))
      (node (ref "U8") (pin "1") (pinfunction "VDD_1") (pintype "power_in"))
      (node (ref "U80") (pin "1") (pinfunction "VDD_1") (pintype "power_in"))
      (node (ref "U81") (pin "1") (pinfunction "VDD_1") (pintype "power_in"))
      (node (ref "U82") (pin "1") (pinfunction "VDD_1") (pintype "power_in"))
      (node (ref "U83") (pin "1") (pinfunction "VDD_1") (pintype "power_in"))
      (node (ref "U84") (pin "1") (pinfunction "VDD_1") (pintype "power_in"))
      (node (ref "U85") (pin "1") (pinfunction "VDD_1") (pintype "power_in"))
      (node (ref "U86") (pin "1") (pinfunction "VDD_1") (pintype "power_in"))
      (node (ref "U87") (pin "1") (pinfunction "VDD_1") (pintype "power_in"))
      (node (ref "U88") (pin "1") (pinfunction "VDD_1") (pintype "power_in"))
      (node (ref "U89") (pin "1") (pinfunction "VDD_1") (pintype "power_in"))
      (node (ref "U9") (pin "1") (pinfunction "VDD_1") (pintype "power_in"))
      (node (ref "U90") (pin "1") (pinfunction "VDD_1") (pintype "power_in"))
      (node (ref "U91") (pin "1") (pinfunction "VDD_1") (pintype "power_in"))
      (node (ref "U92") (pin "1") (pinfunction "VDD_1") (pintype "power_in"))
      (node (ref "U93") (pin "1") (pinfunction "VDD_1") (pintype "power_in"))
      (node (ref "U94") (pin "1") (pinfunction "VDD_1") (pintype "power_in"))
      (node (ref "U95") (pin "1") (pinfunction "VDD_1") (pintype "power_in"))
      (node (ref "U96") (pin "1") (pinfunction "VDD_1") (pintype "power_in"))
      (node (ref "U97") (pin "1") (pinfunction "VDD_1") (pintype "power_in"))
      (node (ref "U98") (pin "1") (pinfunction "VDD_1") (pintype "power_in"))
      (node (ref "U99") (pin "1") (pinfunction "VDD_1") (pintype "power_in"))
    )
    (net (code "223") (name "unconnected-(U40-DOUT-Pad2)") (class "Default")
      (node (ref "U40") (pin "2") (pinfunction "DOUT_2") (pintype "output"))
    )
    (net (code "224") (name "unconnected-(U80-DOUT-Pad2)") (class "Default")
      (node (ref "U80") (pin "2") (pinfunction "DOUT_2") (pintype "output"))
    )
    (net (code "225") (name "unconnected-(U120-DOUT-Pad2)") (class "Default")
      (node (ref "U120") (pin "2") (pinfunction "DOUT_2") (pintype "output"))
    )
    (net (code "226") (name "unconnected-(U160-DOUT-Pad2)") (class "Default")
      (node (ref "U160") (pin "2") (pinfunction "DOUT_2") (pintype "output"))
    )
    (net (code "227") (name "unconnected-(U220-DOUT-Pad2)") (class "Default")
      (node (ref "U220") (pin "2") (pinfunction "DOUT_2") (pintype "output"))
    )
  )
)
